# pcb.net
KiCad netlist of a schematic drawn in EAGLE
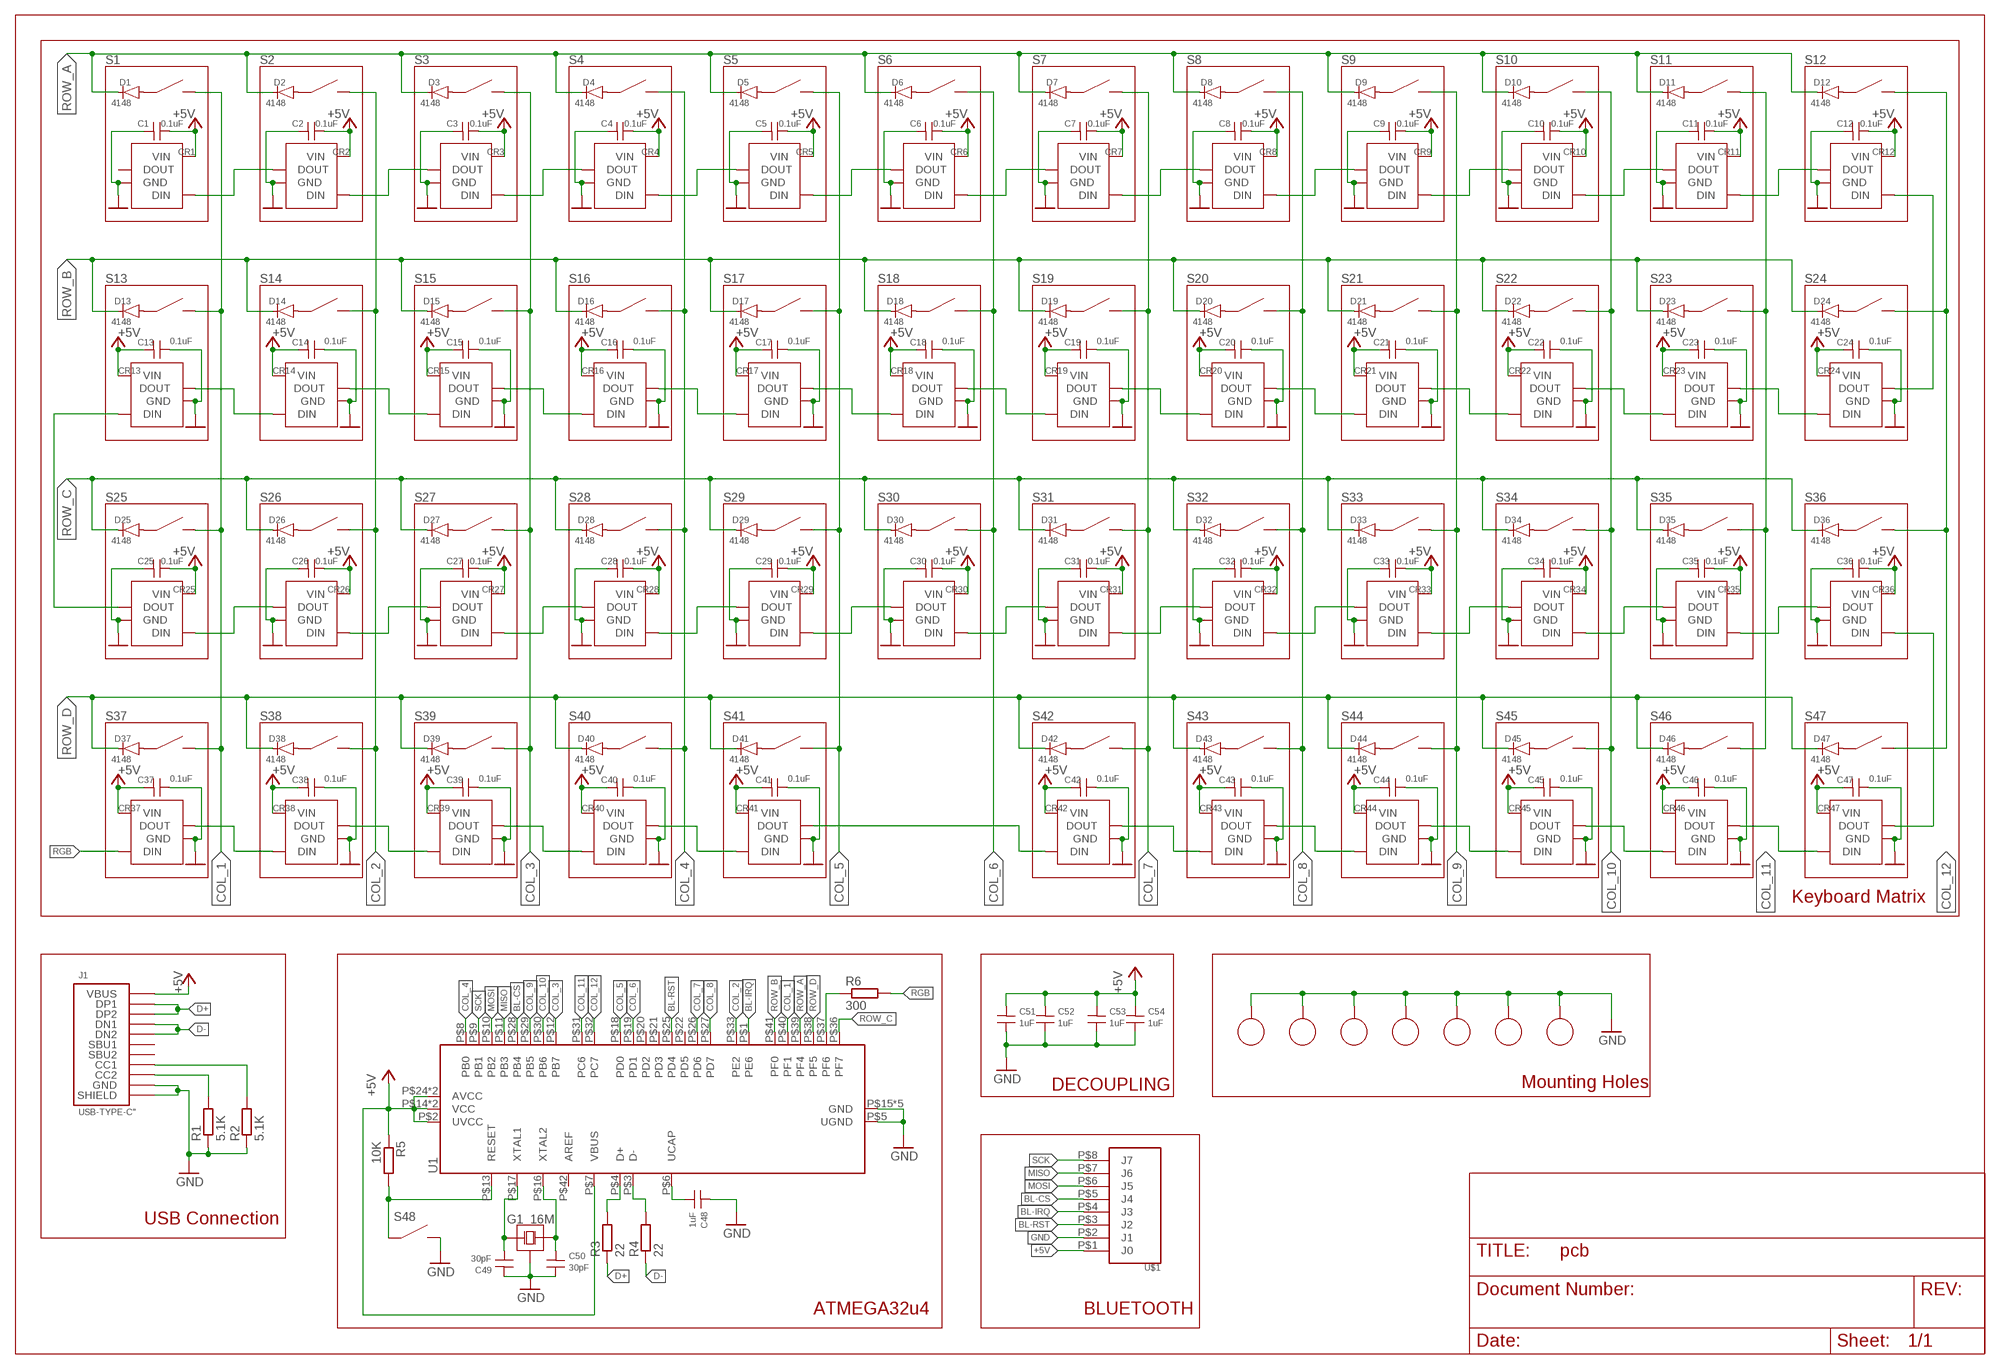
[diagram p0: schematic, sheet 1]

(export (version "E")
  (design (tool "Eeschema 10.0.6"))
  (components
    (comp (ref "C1")
      (value "0.1uF")
      (footprint "eagle-import:C0402")
      (fields
        (field (name "LCSC-PART") "C392963")
        (field (name "MANUFACTURER") "CCTC")
        (field (name "MFGPART#") "TCC0402X7R104K160AT")
      )
      (libsource (lib "eagle-import") (part "C-EU-0402-0.1U"))
    )
    (comp (ref "C2")
      (value "0.1uF")
      (footprint "eagle-import:C0402")
      (fields
        (field (name "LCSC-PART") "C392963")
        (field (name "MANUFACTURER") "CCTC")
        (field (name "MFGPART#") "TCC0402X7R104K160AT")
      )
      (libsource (lib "eagle-import") (part "C-EU-0402-0.1U"))
    )
    (comp (ref "C3")
      (value "0.1uF")
      (footprint "eagle-import:C0402")
      (fields
        (field (name "LCSC-PART") "C392963")
        (field (name "MANUFACTURER") "CCTC")
        (field (name "MFGPART#") "TCC0402X7R104K160AT")
      )
      (libsource (lib "eagle-import") (part "C-EU-0402-0.1U"))
    )
    (comp (ref "C4")
      (value "0.1uF")
      (footprint "eagle-import:C0402")
      (fields
        (field (name "LCSC-PART") "C392963")
        (field (name "MANUFACTURER") "CCTC")
        (field (name "MFGPART#") "TCC0402X7R104K160AT")
      )
      (libsource (lib "eagle-import") (part "C-EU-0402-0.1U"))
    )
    (comp (ref "C5")
      (value "0.1uF")
      (footprint "eagle-import:C0402")
      (fields
        (field (name "LCSC-PART") "C392963")
        (field (name "MANUFACTURER") "CCTC")
        (field (name "MFGPART#") "TCC0402X7R104K160AT")
      )
      (libsource (lib "eagle-import") (part "C-EU-0402-0.1U"))
    )
    (comp (ref "C6")
      (value "0.1uF")
      (footprint "eagle-import:C0402")
      (fields
        (field (name "LCSC-PART") "C392963")
        (field (name "MANUFACTURER") "CCTC")
        (field (name "MFGPART#") "TCC0402X7R104K160AT")
      )
      (libsource (lib "eagle-import") (part "C-EU-0402-0.1U"))
    )
    (comp (ref "C7")
      (value "0.1uF")
      (footprint "eagle-import:C0402")
      (fields
        (field (name "LCSC-PART") "C392963")
        (field (name "MANUFACTURER") "CCTC")
        (field (name "MFGPART#") "TCC0402X7R104K160AT")
      )
      (libsource (lib "eagle-import") (part "C-EU-0402-0.1U"))
    )
    (comp (ref "C8")
      (value "0.1uF")
      (footprint "eagle-import:C0402")
      (fields
        (field (name "LCSC-PART") "C392963")
        (field (name "MANUFACTURER") "CCTC")
        (field (name "MFGPART#") "TCC0402X7R104K160AT")
      )
      (libsource (lib "eagle-import") (part "C-EU-0402-0.1U"))
    )
    (comp (ref "C9")
      (value "0.1uF")
      (footprint "eagle-import:C0402")
      (fields
        (field (name "LCSC-PART") "C392963")
        (field (name "MANUFACTURER") "CCTC")
        (field (name "MFGPART#") "TCC0402X7R104K160AT")
      )
      (libsource (lib "eagle-import") (part "C-EU-0402-0.1U"))
    )
    (comp (ref "C10")
      (value "0.1uF")
      (footprint "eagle-import:C0402")
      (fields
        (field (name "LCSC-PART") "C392963")
        (field (name "MANUFACTURER") "CCTC")
        (field (name "MFGPART#") "TCC0402X7R104K160AT")
      )
      (libsource (lib "eagle-import") (part "C-EU-0402-0.1U"))
    )
    (comp (ref "C11")
      (value "0.1uF")
      (footprint "eagle-import:C0402")
      (fields
        (field (name "LCSC-PART") "C392963")
        (field (name "MANUFACTURER") "CCTC")
        (field (name "MFGPART#") "TCC0402X7R104K160AT")
      )
      (libsource (lib "eagle-import") (part "C-EU-0402-0.1U"))
    )
    (comp (ref "C12")
      (value "0.1uF")
      (footprint "eagle-import:C0402")
      (fields
        (field (name "LCSC-PART") "C392963")
        (field (name "MANUFACTURER") "CCTC")
        (field (name "MFGPART#") "TCC0402X7R104K160AT")
      )
      (libsource (lib "eagle-import") (part "C-EU-0402-0.1U"))
    )
    (comp (ref "C13")
      (value "0.1uF")
      (footprint "eagle-import:C0402")
      (fields
        (field (name "LCSC-PART") "C392963")
        (field (name "MANUFACTURER") "CCTC")
        (field (name "MFGPART#") "TCC0402X7R104K160AT")
      )
      (libsource (lib "eagle-import") (part "C-EU-0402-0.1U"))
    )
    (comp (ref "C14")
      (value "0.1uF")
      (footprint "eagle-import:C0402")
      (fields
        (field (name "LCSC-PART") "C392963")
        (field (name "MANUFACTURER") "CCTC")
        (field (name "MFGPART#") "TCC0402X7R104K160AT")
      )
      (libsource (lib "eagle-import") (part "C-EU-0402-0.1U"))
    )
    (comp (ref "C15")
      (value "0.1uF")
      (footprint "eagle-import:C0402")
      (fields
        (field (name "LCSC-PART") "C392963")
        (field (name "MANUFACTURER") "CCTC")
        (field (name "MFGPART#") "TCC0402X7R104K160AT")
      )
      (libsource (lib "eagle-import") (part "C-EU-0402-0.1U"))
    )
    (comp (ref "C16")
      (value "0.1uF")
      (footprint "eagle-import:C0402")
      (fields
        (field (name "LCSC-PART") "C392963")
        (field (name "MANUFACTURER") "CCTC")
        (field (name "MFGPART#") "TCC0402X7R104K160AT")
      )
      (libsource (lib "eagle-import") (part "C-EU-0402-0.1U"))
    )
    (comp (ref "C17")
      (value "0.1uF")
      (footprint "eagle-import:C0402")
      (fields
        (field (name "LCSC-PART") "C392963")
        (field (name "MANUFACTURER") "CCTC")
        (field (name "MFGPART#") "TCC0402X7R104K160AT")
      )
      (libsource (lib "eagle-import") (part "C-EU-0402-0.1U"))
    )
    (comp (ref "C18")
      (value "0.1uF")
      (footprint "eagle-import:C0402")
      (fields
        (field (name "LCSC-PART") "C392963")
        (field (name "MANUFACTURER") "CCTC")
        (field (name "MFGPART#") "TCC0402X7R104K160AT")
      )
      (libsource (lib "eagle-import") (part "C-EU-0402-0.1U"))
    )
    (comp (ref "C19")
      (value "0.1uF")
      (footprint "eagle-import:C0402")
      (fields
        (field (name "LCSC-PART") "C392963")
        (field (name "MANUFACTURER") "CCTC")
        (field (name "MFGPART#") "TCC0402X7R104K160AT")
      )
      (libsource (lib "eagle-import") (part "C-EU-0402-0.1U"))
    )
    (comp (ref "C20")
      (value "0.1uF")
      (footprint "eagle-import:C0402")
      (fields
        (field (name "LCSC-PART") "C392963")
        (field (name "MANUFACTURER") "CCTC")
        (field (name "MFGPART#") "TCC0402X7R104K160AT")
      )
      (libsource (lib "eagle-import") (part "C-EU-0402-0.1U"))
    )
    (comp (ref "C21")
      (value "0.1uF")
      (footprint "eagle-import:C0402")
      (fields
        (field (name "LCSC-PART") "C392963")
        (field (name "MANUFACTURER") "CCTC")
        (field (name "MFGPART#") "TCC0402X7R104K160AT")
      )
      (libsource (lib "eagle-import") (part "C-EU-0402-0.1U"))
    )
    (comp (ref "C22")
      (value "0.1uF")
      (footprint "eagle-import:C0402")
      (fields
        (field (name "LCSC-PART") "C392963")
        (field (name "MANUFACTURER") "CCTC")
        (field (name "MFGPART#") "TCC0402X7R104K160AT")
      )
      (libsource (lib "eagle-import") (part "C-EU-0402-0.1U"))
    )
    (comp (ref "C23")
      (value "0.1uF")
      (footprint "eagle-import:C0402")
      (fields
        (field (name "LCSC-PART") "C392963")
        (field (name "MANUFACTURER") "CCTC")
        (field (name "MFGPART#") "TCC0402X7R104K160AT")
      )
      (libsource (lib "eagle-import") (part "C-EU-0402-0.1U"))
    )
    (comp (ref "C24")
      (value "0.1uF")
      (footprint "eagle-import:C0402")
      (fields
        (field (name "LCSC-PART") "C392963")
        (field (name "MANUFACTURER") "CCTC")
        (field (name "MFGPART#") "TCC0402X7R104K160AT")
      )
      (libsource (lib "eagle-import") (part "C-EU-0402-0.1U"))
    )
    (comp (ref "C25")
      (value "0.1uF")
      (footprint "eagle-import:C0402")
      (fields
        (field (name "LCSC-PART") "C392963")
        (field (name "MANUFACTURER") "CCTC")
        (field (name "MFGPART#") "TCC0402X7R104K160AT")
      )
      (libsource (lib "eagle-import") (part "C-EU-0402-0.1U"))
    )
    (comp (ref "C26")
      (value "0.1uF")
      (footprint "eagle-import:C0402")
      (fields
        (field (name "LCSC-PART") "C392963")
        (field (name "MANUFACTURER") "CCTC")
        (field (name "MFGPART#") "TCC0402X7R104K160AT")
      )
      (libsource (lib "eagle-import") (part "C-EU-0402-0.1U"))
    )
    (comp (ref "C27")
      (value "0.1uF")
      (footprint "eagle-import:C0402")
      (fields
        (field (name "LCSC-PART") "C392963")
        (field (name "MANUFACTURER") "CCTC")
        (field (name "MFGPART#") "TCC0402X7R104K160AT")
      )
      (libsource (lib "eagle-import") (part "C-EU-0402-0.1U"))
    )
    (comp (ref "C28")
      (value "0.1uF")
      (footprint "eagle-import:C0402")
      (fields
        (field (name "LCSC-PART") "C392963")
        (field (name "MANUFACTURER") "CCTC")
        (field (name "MFGPART#") "TCC0402X7R104K160AT")
      )
      (libsource (lib "eagle-import") (part "C-EU-0402-0.1U"))
    )
    (comp (ref "C29")
      (value "0.1uF")
      (footprint "eagle-import:C0402")
      (fields
        (field (name "LCSC-PART") "C392963")
        (field (name "MANUFACTURER") "CCTC")
        (field (name "MFGPART#") "TCC0402X7R104K160AT")
      )
      (libsource (lib "eagle-import") (part "C-EU-0402-0.1U"))
    )
    (comp (ref "C30")
      (value "0.1uF")
      (footprint "eagle-import:C0402")
      (fields
        (field (name "LCSC-PART") "C392963")
        (field (name "MANUFACTURER") "CCTC")
        (field (name "MFGPART#") "TCC0402X7R104K160AT")
      )
      (libsource (lib "eagle-import") (part "C-EU-0402-0.1U"))
    )
    (comp (ref "C31")
      (value "0.1uF")
      (footprint "eagle-import:C0402")
      (fields
        (field (name "LCSC-PART") "C392963")
        (field (name "MANUFACTURER") "CCTC")
        (field (name "MFGPART#") "TCC0402X7R104K160AT")
      )
      (libsource (lib "eagle-import") (part "C-EU-0402-0.1U"))
    )
    (comp (ref "C32")
      (value "0.1uF")
      (footprint "eagle-import:C0402")
      (fields
        (field (name "LCSC-PART") "C392963")
        (field (name "MANUFACTURER") "CCTC")
        (field (name "MFGPART#") "TCC0402X7R104K160AT")
      )
      (libsource (lib "eagle-import") (part "C-EU-0402-0.1U"))
    )
    (comp (ref "C33")
      (value "0.1uF")
      (footprint "eagle-import:C0402")
      (fields
        (field (name "LCSC-PART") "C392963")
        (field (name "MANUFACTURER") "CCTC")
        (field (name "MFGPART#") "TCC0402X7R104K160AT")
      )
      (libsource (lib "eagle-import") (part "C-EU-0402-0.1U"))
    )
    (comp (ref "C34")
      (value "0.1uF")
      (footprint "eagle-import:C0402")
      (fields
        (field (name "LCSC-PART") "C392963")
        (field (name "MANUFACTURER") "CCTC")
        (field (name "MFGPART#") "TCC0402X7R104K160AT")
      )
      (libsource (lib "eagle-import") (part "C-EU-0402-0.1U"))
    )
    (comp (ref "C35")
      (value "0.1uF")
      (footprint "eagle-import:C0402")
      (fields
        (field (name "LCSC-PART") "C392963")
        (field (name "MANUFACTURER") "CCTC")
        (field (name "MFGPART#") "TCC0402X7R104K160AT")
      )
      (libsource (lib "eagle-import") (part "C-EU-0402-0.1U"))
    )
    (comp (ref "C36")
      (value "0.1uF")
      (footprint "eagle-import:C0402")
      (fields
        (field (name "LCSC-PART") "C392963")
        (field (name "MANUFACTURER") "CCTC")
        (field (name "MFGPART#") "TCC0402X7R104K160AT")
      )
      (libsource (lib "eagle-import") (part "C-EU-0402-0.1U"))
    )
    (comp (ref "C37")
      (value "0.1uF")
      (footprint "eagle-import:C0402")
      (fields
        (field (name "LCSC-PART") "C392963")
        (field (name "MANUFACTURER") "CCTC")
        (field (name "MFGPART#") "TCC0402X7R104K160AT")
      )
      (libsource (lib "eagle-import") (part "C-EU-0402-0.1U"))
    )
    (comp (ref "C38")
      (value "0.1uF")
      (footprint "eagle-import:C0402")
      (fields
        (field (name "LCSC-PART") "C392963")
        (field (name "MANUFACTURER") "CCTC")
        (field (name "MFGPART#") "TCC0402X7R104K160AT")
      )
      (libsource (lib "eagle-import") (part "C-EU-0402-0.1U"))
    )
    (comp (ref "C39")
      (value "0.1uF")
      (footprint "eagle-import:C0402")
      (fields
        (field (name "LCSC-PART") "C392963")
        (field (name "MANUFACTURER") "CCTC")
        (field (name "MFGPART#") "TCC0402X7R104K160AT")
      )
      (libsource (lib "eagle-import") (part "C-EU-0402-0.1U"))
    )
    (comp (ref "C40")
      (value "0.1uF")
      (footprint "eagle-import:C0402")
      (fields
        (field (name "LCSC-PART") "C392963")
        (field (name "MANUFACTURER") "CCTC")
        (field (name "MFGPART#") "TCC0402X7R104K160AT")
      )
      (libsource (lib "eagle-import") (part "C-EU-0402-0.1U"))
    )
    (comp (ref "C41")
      (value "0.1uF")
      (footprint "eagle-import:C0402")
      (fields
        (field (name "LCSC-PART") "C392963")
        (field (name "MANUFACTURER") "CCTC")
        (field (name "MFGPART#") "TCC0402X7R104K160AT")
      )
      (libsource (lib "eagle-import") (part "C-EU-0402-0.1U"))
    )
    (comp (ref "C42")
      (value "0.1uF")
      (footprint "eagle-import:C0402")
      (fields
        (field (name "LCSC-PART") "C392963")
        (field (name "MANUFACTURER") "CCTC")
        (field (name "MFGPART#") "TCC0402X7R104K160AT")
      )
      (libsource (lib "eagle-import") (part "C-EU-0402-0.1U"))
    )
    (comp (ref "C43")
      (value "0.1uF")
      (footprint "eagle-import:C0402")
      (fields
        (field (name "LCSC-PART") "C392963")
        (field (name "MANUFACTURER") "CCTC")
        (field (name "MFGPART#") "TCC0402X7R104K160AT")
      )
      (libsource (lib "eagle-import") (part "C-EU-0402-0.1U"))
    )
    (comp (ref "C44")
      (value "0.1uF")
      (footprint "eagle-import:C0402")
      (fields
        (field (name "LCSC-PART") "C392963")
        (field (name "MANUFACTURER") "CCTC")
        (field (name "MFGPART#") "TCC0402X7R104K160AT")
      )
      (libsource (lib "eagle-import") (part "C-EU-0402-0.1U"))
    )
    (comp (ref "C45")
      (value "0.1uF")
      (footprint "eagle-import:C0402")
      (fields
        (field (name "LCSC-PART") "C392963")
        (field (name "MANUFACTURER") "CCTC")
        (field (name "MFGPART#") "TCC0402X7R104K160AT")
      )
      (libsource (lib "eagle-import") (part "C-EU-0402-0.1U"))
    )
    (comp (ref "C46")
      (value "0.1uF")
      (footprint "eagle-import:C0402")
      (fields
        (field (name "LCSC-PART") "C392963")
        (field (name "MANUFACTURER") "CCTC")
        (field (name "MFGPART#") "TCC0402X7R104K160AT")
      )
      (libsource (lib "eagle-import") (part "C-EU-0402-0.1U"))
    )
    (comp (ref "C47")
      (value "0.1uF")
      (footprint "eagle-import:C0402")
      (fields
        (field (name "LCSC-PART") "C392963")
        (field (name "MANUFACTURER") "CCTC")
        (field (name "MFGPART#") "TCC0402X7R104K160AT")
      )
      (libsource (lib "eagle-import") (part "C-EU-0402-0.1U"))
    )
    (comp (ref "C48")
      (value "1uF")
      (footprint "eagle-import:C0402")
      (fields
        (field (name "LCSC-PART") "C107372")
        (field (name "MANUFACTURER") "Samsung Electro-Mechanics")
        (field (name "MFGPART#") "CL05A105KQ5NNNC")
      )
      (libsource (lib "eagle-import") (part "C-EU-0402-1U"))
    )
    (comp (ref "C49")
      (value "30pF")
      (footprint "eagle-import:C0402")
      (fields
        (field (name "LCSC-PART") "C107004")
        (field (name "MANUFACTURER") "YAGEO")
        (field (name "MFGPART#") "CC0402JRNPO9BN300")
      )
      (libsource (lib "eagle-import") (part "C-EU-0402-30P"))
    )
    (comp (ref "C50")
      (value "30pF")
      (footprint "eagle-import:C0402")
      (fields
        (field (name "LCSC-PART") "C107004")
        (field (name "MANUFACTURER") "YAGEO")
        (field (name "MFGPART#") "CC0402JRNPO9BN300")
      )
      (libsource (lib "eagle-import") (part "C-EU-0402-30P"))
    )
    (comp (ref "C51")
      (value "1uF")
      (footprint "eagle-import:C0402")
      (fields
        (field (name "LCSC-PART") "C107372")
        (field (name "MANUFACTURER") "Samsung Electro-Mechanics")
        (field (name "MFGPART#") "CL05A105KQ5NNNC")
      )
      (libsource (lib "eagle-import") (part "C-EU-0402-1U"))
    )
    (comp (ref "C52")
      (value "1uF")
      (footprint "eagle-import:C0402")
      (fields
        (field (name "LCSC-PART") "C107372")
        (field (name "MANUFACTURER") "Samsung Electro-Mechanics")
        (field (name "MFGPART#") "CL05A105KQ5NNNC")
      )
      (libsource (lib "eagle-import") (part "C-EU-0402-1U"))
    )
    (comp (ref "C53")
      (value "1uF")
      (footprint "eagle-import:C0402")
      (fields
        (field (name "LCSC-PART") "C107372")
        (field (name "MANUFACTURER") "Samsung Electro-Mechanics")
        (field (name "MFGPART#") "CL05A105KQ5NNNC")
      )
      (libsource (lib "eagle-import") (part "C-EU-0402-1U"))
    )
    (comp (ref "C54")
      (value "1uF")
      (footprint "eagle-import:C0402")
      (fields
        (field (name "LCSC-PART") "C107372")
        (field (name "MANUFACTURER") "Samsung Electro-Mechanics")
        (field (name "MFGPART#") "CL05A105KQ5NNNC")
      )
      (libsource (lib "eagle-import") (part "C-EU-0402-1U"))
    )
    (comp (ref "CR1")
      (value "SK6812MINI-E")
      (footprint "eagle-import:SK6812MINI-E")
      (fields (field (name "SPICEPREFIX") "E"))
      (libsource (lib "eagle-import") (part "SK6812MINI-E"))
    )
    (comp (ref "CR2")
      (value "SK6812MINI-E")
      (footprint "eagle-import:SK6812MINI-E")
      (fields (field (name "SPICEPREFIX") "E"))
      (libsource (lib "eagle-import") (part "SK6812MINI-E"))
    )
    (comp (ref "CR3")
      (value "SK6812MINI-E")
      (footprint "eagle-import:SK6812MINI-E")
      (fields (field (name "SPICEPREFIX") "E"))
      (libsource (lib "eagle-import") (part "SK6812MINI-E"))
    )
    (comp (ref "CR4")
      (value "SK6812MINI-E")
      (footprint "eagle-import:SK6812MINI-E")
      (fields (field (name "SPICEPREFIX") "E"))
      (libsource (lib "eagle-import") (part "SK6812MINI-E"))
    )
    (comp (ref "CR5")
      (value "SK6812MINI-E")
      (footprint "eagle-import:SK6812MINI-E")
      (fields (field (name "SPICEPREFIX") "E"))
      (libsource (lib "eagle-import") (part "SK6812MINI-E"))
    )
    (comp (ref "CR6")
      (value "SK6812MINI-E")
      (footprint "eagle-import:SK6812MINI-E")
      (fields (field (name "SPICEPREFIX") "E"))
      (libsource (lib "eagle-import") (part "SK6812MINI-E"))
    )
    (comp (ref "CR7")
      (value "SK6812MINI-E")
      (footprint "eagle-import:SK6812MINI-E")
      (fields (field (name "SPICEPREFIX") "E"))
      (libsource (lib "eagle-import") (part "SK6812MINI-E"))
    )
    (comp (ref "CR8")
      (value "SK6812MINI-E")
      (footprint "eagle-import:SK6812MINI-E")
      (fields (field (name "SPICEPREFIX") "E"))
      (libsource (lib "eagle-import") (part "SK6812MINI-E"))
    )
    (comp (ref "CR9")
      (value "SK6812MINI-E")
      (footprint "eagle-import:SK6812MINI-E")
      (fields (field (name "SPICEPREFIX") "E"))
      (libsource (lib "eagle-import") (part "SK6812MINI-E"))
    )
    (comp (ref "CR10")
      (value "SK6812MINI-E")
      (footprint "eagle-import:SK6812MINI-E")
      (fields (field (name "SPICEPREFIX") "E"))
      (libsource (lib "eagle-import") (part "SK6812MINI-E"))
    )
    (comp (ref "CR11")
      (value "SK6812MINI-E")
      (footprint "eagle-import:SK6812MINI-E")
      (fields (field (name "SPICEPREFIX") "E"))
      (libsource (lib "eagle-import") (part "SK6812MINI-E"))
    )
    (comp (ref "CR12")
      (value "SK6812MINI-E")
      (footprint "eagle-import:SK6812MINI-E")
      (fields (field (name "SPICEPREFIX") "E"))
      (libsource (lib "eagle-import") (part "SK6812MINI-E"))
    )
    (comp (ref "CR13")
      (value "SK6812MINI-E")
      (footprint "eagle-import:SK6812MINI-E")
      (fields (field (name "SPICEPREFIX") "E"))
      (libsource (lib "eagle-import") (part "SK6812MINI-E"))
    )
    (comp (ref "CR14")
      (value "SK6812MINI-E")
      (footprint "eagle-import:SK6812MINI-E")
      (fields (field (name "SPICEPREFIX") "E"))
      (libsource (lib "eagle-import") (part "SK6812MINI-E"))
    )
    (comp (ref "CR15")
      (value "SK6812MINI-E")
      (footprint "eagle-import:SK6812MINI-E")
      (fields (field (name "SPICEPREFIX") "E"))
      (libsource (lib "eagle-import") (part "SK6812MINI-E"))
    )
    (comp (ref "CR16")
      (value "SK6812MINI-E")
      (footprint "eagle-import:SK6812MINI-E")
      (fields (field (name "SPICEPREFIX") "E"))
      (libsource (lib "eagle-import") (part "SK6812MINI-E"))
    )
    (comp (ref "CR17")
      (value "SK6812MINI-E")
      (footprint "eagle-import:SK6812MINI-E")
      (fields (field (name "SPICEPREFIX") "E"))
      (libsource (lib "eagle-import") (part "SK6812MINI-E"))
    )
    (comp (ref "CR18")
      (value "SK6812MINI-E")
      (footprint "eagle-import:SK6812MINI-E")
      (fields (field (name "SPICEPREFIX") "E"))
      (libsource (lib "eagle-import") (part "SK6812MINI-E"))
    )
    (comp (ref "CR19")
      (value "SK6812MINI-E")
      (footprint "eagle-import:SK6812MINI-E")
      (fields (field (name "SPICEPREFIX") "E"))
      (libsource (lib "eagle-import") (part "SK6812MINI-E"))
    )
    (comp (ref "CR20")
      (value "SK6812MINI-E")
      (footprint "eagle-import:SK6812MINI-E")
      (fields (field (name "SPICEPREFIX") "E"))
      (libsource (lib "eagle-import") (part "SK6812MINI-E"))
    )
    (comp (ref "CR21")
      (value "SK6812MINI-E")
      (footprint "eagle-import:SK6812MINI-E")
      (fields (field (name "SPICEPREFIX") "E"))
      (libsource (lib "eagle-import") (part "SK6812MINI-E"))
    )
    (comp (ref "CR22")
      (value "SK6812MINI-E")
      (footprint "eagle-import:SK6812MINI-E")
      (fields (field (name "SPICEPREFIX") "E"))
      (libsource (lib "eagle-import") (part "SK6812MINI-E"))
    )
    (comp (ref "CR23")
      (value "SK6812MINI-E")
      (footprint "eagle-import:SK6812MINI-E")
      (fields (field (name "SPICEPREFIX") "E"))
      (libsource (lib "eagle-import") (part "SK6812MINI-E"))
    )
    (comp (ref "CR24")
      (value "SK6812MINI-E")
      (footprint "eagle-import:SK6812MINI-E")
      (fields (field (name "SPICEPREFIX") "E"))
      (libsource (lib "eagle-import") (part "SK6812MINI-E"))
    )
    (comp (ref "CR25")
      (value "SK6812MINI-E")
      (footprint "eagle-import:SK6812MINI-E")
      (fields (field (name "SPICEPREFIX") "E"))
      (libsource (lib "eagle-import") (part "SK6812MINI-E"))
    )
    (comp (ref "CR26")
      (value "SK6812MINI-E")
      (footprint "eagle-import:SK6812MINI-E")
      (fields (field (name "SPICEPREFIX") "E"))
      (libsource (lib "eagle-import") (part "SK6812MINI-E"))
    )
    (comp (ref "CR27")
      (value "SK6812MINI-E")
      (footprint "eagle-import:SK6812MINI-E")
      (fields (field (name "SPICEPREFIX") "E"))
      (libsource (lib "eagle-import") (part "SK6812MINI-E"))
    )
    (comp (ref "CR28")
      (value "SK6812MINI-E")
      (footprint "eagle-import:SK6812MINI-E")
      (fields (field (name "SPICEPREFIX") "E"))
      (libsource (lib "eagle-import") (part "SK6812MINI-E"))
    )
    (comp (ref "CR29")
      (value "SK6812MINI-E")
      (footprint "eagle-import:SK6812MINI-E")
      (fields (field (name "SPICEPREFIX") "E"))
      (libsource (lib "eagle-import") (part "SK6812MINI-E"))
    )
    (comp (ref "CR30")
      (value "SK6812MINI-E")
      (footprint "eagle-import:SK6812MINI-E")
      (fields (field (name "SPICEPREFIX") "E"))
      (libsource (lib "eagle-import") (part "SK6812MINI-E"))
    )
    (comp (ref "CR31")
      (value "SK6812MINI-E")
      (footprint "eagle-import:SK6812MINI-E")
      (fields (field (name "SPICEPREFIX") "E"))
      (libsource (lib "eagle-import") (part "SK6812MINI-E"))
    )
    (comp (ref "CR32")
      (value "SK6812MINI-E")
      (footprint "eagle-import:SK6812MINI-E")
      (fields (field (name "SPICEPREFIX") "E"))
      (libsource (lib "eagle-import") (part "SK6812MINI-E"))
    )
    (comp (ref "CR33")
      (value "SK6812MINI-E")
      (footprint "eagle-import:SK6812MINI-E")
      (fields (field (name "SPICEPREFIX") "E"))
      (libsource (lib "eagle-import") (part "SK6812MINI-E"))
    )
    (comp (ref "CR34")
      (value "SK6812MINI-E")
      (footprint "eagle-import:SK6812MINI-E")
      (fields (field (name "SPICEPREFIX") "E"))
      (libsource (lib "eagle-import") (part "SK6812MINI-E"))
    )
    (comp (ref "CR35")
      (value "SK6812MINI-E")
      (footprint "eagle-import:SK6812MINI-E")
      (fields (field (name "SPICEPREFIX") "E"))
      (libsource (lib "eagle-import") (part "SK6812MINI-E"))
    )
    (comp (ref "CR36")
      (value "SK6812MINI-E")
      (footprint "eagle-import:SK6812MINI-E")
      (fields (field (name "SPICEPREFIX") "E"))
      (libsource (lib "eagle-import") (part "SK6812MINI-E"))
    )
    (comp (ref "CR37")
      (value "SK6812MINI-E")
      (footprint "eagle-import:SK6812MINI-E")
      (fields (field (name "SPICEPREFIX") "E"))
      (libsource (lib "eagle-import") (part "SK6812MINI-E"))
    )
    (comp (ref "CR38")
      (value "SK6812MINI-E")
      (footprint "eagle-import:SK6812MINI-E")
      (fields (field (name "SPICEPREFIX") "E"))
      (libsource (lib "eagle-import") (part "SK6812MINI-E"))
    )
    (comp (ref "CR39")
      (value "SK6812MINI-E")
      (footprint "eagle-import:SK6812MINI-E")
      (fields (field (name "SPICEPREFIX") "E"))
      (libsource (lib "eagle-import") (part "SK6812MINI-E"))
    )
    (comp (ref "CR40")
      (value "SK6812MINI-E")
      (footprint "eagle-import:SK6812MINI-E")
      (fields (field (name "SPICEPREFIX") "E"))
      (libsource (lib "eagle-import") (part "SK6812MINI-E"))
    )
    (comp (ref "CR41")
      (value "SK6812MINI-E")
      (footprint "eagle-import:SK6812MINI-E")
      (fields (field (name "SPICEPREFIX") "E"))
      (libsource (lib "eagle-import") (part "SK6812MINI-E"))
    )
    (comp (ref "CR42")
      (value "SK6812MINI-E")
      (footprint "eagle-import:SK6812MINI-E")
      (fields (field (name "SPICEPREFIX") "E"))
      (libsource (lib "eagle-import") (part "SK6812MINI-E"))
    )
    (comp (ref "CR43")
      (value "SK6812MINI-E")
      (footprint "eagle-import:SK6812MINI-E")
      (fields (field (name "SPICEPREFIX") "E"))
      (libsource (lib "eagle-import") (part "SK6812MINI-E"))
    )
    (comp (ref "CR44")
      (value "SK6812MINI-E")
      (footprint "eagle-import:SK6812MINI-E")
      (fields (field (name "SPICEPREFIX") "E"))
      (libsource (lib "eagle-import") (part "SK6812MINI-E"))
    )
    (comp (ref "CR45")
      (value "SK6812MINI-E")
      (footprint "eagle-import:SK6812MINI-E")
      (fields (field (name "SPICEPREFIX") "E"))
      (libsource (lib "eagle-import") (part "SK6812MINI-E"))
    )
    (comp (ref "CR46")
      (value "SK6812MINI-E")
      (footprint "eagle-import:SK6812MINI-E")
      (fields (field (name "SPICEPREFIX") "E"))
      (libsource (lib "eagle-import") (part "SK6812MINI-E"))
    )
    (comp (ref "CR47")
      (value "SK6812MINI-E")
      (footprint "eagle-import:SK6812MINI-E")
      (fields (field (name "SPICEPREFIX") "E"))
      (libsource (lib "eagle-import") (part "SK6812MINI-E"))
    )
    (comp (ref "D1")
      (value "4148")
      (footprint "eagle-import:MINI_MELF")
      (fields
        (field (name "LCSC-PART") "C402260")
        (field (name "MANUFACTURER") "LGE")
        (field (name "MFGPART#") "LL4148")
        (field (name "SPICEPREFIX") "D")
      )
      (libsource (lib "eagle-import") (part "DIODE-MINI-MELF-4148"))
    )
    (comp (ref "D2")
      (value "4148")
      (footprint "eagle-import:MINI_MELF")
      (fields
        (field (name "LCSC-PART") "C402260")
        (field (name "MANUFACTURER") "LGE")
        (field (name "MFGPART#") "LL4148")
        (field (name "SPICEPREFIX") "D")
      )
      (libsource (lib "eagle-import") (part "DIODE-MINI-MELF-4148"))
    )
    (comp (ref "D3")
      (value "4148")
      (footprint "eagle-import:MINI_MELF")
      (fields
        (field (name "LCSC-PART") "C402260")
        (field (name "MANUFACTURER") "LGE")
        (field (name "MFGPART#") "LL4148")
        (field (name "SPICEPREFIX") "D")
      )
      (libsource (lib "eagle-import") (part "DIODE-MINI-MELF-4148"))
    )
    (comp (ref "D4")
      (value "4148")
      (footprint "eagle-import:MINI_MELF")
      (fields
        (field (name "LCSC-PART") "C402260")
        (field (name "MANUFACTURER") "LGE")
        (field (name "MFGPART#") "LL4148")
        (field (name "SPICEPREFIX") "D")
      )
      (libsource (lib "eagle-import") (part "DIODE-MINI-MELF-4148"))
    )
    (comp (ref "D5")
      (value "4148")
      (footprint "eagle-import:MINI_MELF")
      (fields
        (field (name "LCSC-PART") "C402260")
        (field (name "MANUFACTURER") "LGE")
        (field (name "MFGPART#") "LL4148")
        (field (name "SPICEPREFIX") "D")
      )
      (libsource (lib "eagle-import") (part "DIODE-MINI-MELF-4148"))
    )
    (comp (ref "D6")
      (value "4148")
      (footprint "eagle-import:MINI_MELF")
      (fields
        (field (name "LCSC-PART") "C402260")
        (field (name "MANUFACTURER") "LGE")
        (field (name "MFGPART#") "LL4148")
        (field (name "SPICEPREFIX") "D")
      )
      (libsource (lib "eagle-import") (part "DIODE-MINI-MELF-4148"))
    )
    (comp (ref "D7")
      (value "4148")
      (footprint "eagle-import:MINI_MELF")
      (fields
        (field (name "LCSC-PART") "C402260")
        (field (name "MANUFACTURER") "LGE")
        (field (name "MFGPART#") "LL4148")
        (field (name "SPICEPREFIX") "D")
      )
      (libsource (lib "eagle-import") (part "DIODE-MINI-MELF-4148"))
    )
    (comp (ref "D8")
      (value "4148")
      (footprint "eagle-import:MINI_MELF")
      (fields
        (field (name "LCSC-PART") "C402260")
        (field (name "MANUFACTURER") "LGE")
        (field (name "MFGPART#") "LL4148")
        (field (name "SPICEPREFIX") "D")
      )
      (libsource (lib "eagle-import") (part "DIODE-MINI-MELF-4148"))
    )
    (comp (ref "D9")
      (value "4148")
      (footprint "eagle-import:MINI_MELF")
      (fields
        (field (name "LCSC-PART") "C402260")
        (field (name "MANUFACTURER") "LGE")
        (field (name "MFGPART#") "LL4148")
        (field (name "SPICEPREFIX") "D")
      )
      (libsource (lib "eagle-import") (part "DIODE-MINI-MELF-4148"))
    )
    (comp (ref "D10")
      (value "4148")
      (footprint "eagle-import:MINI_MELF")
      (fields
        (field (name "LCSC-PART") "C402260")
        (field (name "MANUFACTURER") "LGE")
        (field (name "MFGPART#") "LL4148")
        (field (name "SPICEPREFIX") "D")
      )
      (libsource (lib "eagle-import") (part "DIODE-MINI-MELF-4148"))
    )
    (comp (ref "D11")
      (value "4148")
      (footprint "eagle-import:MINI_MELF")
      (fields
        (field (name "LCSC-PART") "C402260")
        (field (name "MANUFACTURER") "LGE")
        (field (name "MFGPART#") "LL4148")
        (field (name "SPICEPREFIX") "D")
      )
      (libsource (lib "eagle-import") (part "DIODE-MINI-MELF-4148"))
    )
    (comp (ref "D12")
      (value "4148")
      (footprint "eagle-import:MINI_MELF")
      (fields
        (field (name "LCSC-PART") "C402260")
        (field (name "MANUFACTURER") "LGE")
        (field (name "MFGPART#") "LL4148")
        (field (name "SPICEPREFIX") "D")
      )
      (libsource (lib "eagle-import") (part "DIODE-MINI-MELF-4148"))
    )
    (comp (ref "D13")
      (value "4148")
      (footprint "eagle-import:MINI_MELF")
      (fields
        (field (name "LCSC-PART") "C402260")
        (field (name "MANUFACTURER") "LGE")
        (field (name "MFGPART#") "LL4148")
        (field (name "SPICEPREFIX") "D")
      )
      (libsource (lib "eagle-import") (part "DIODE-MINI-MELF-4148"))
    )
    (comp (ref "D14")
      (value "4148")
      (footprint "eagle-import:MINI_MELF")
      (fields
        (field (name "LCSC-PART") "C402260")
        (field (name "MANUFACTURER") "LGE")
        (field (name "MFGPART#") "LL4148")
        (field (name "SPICEPREFIX") "D")
      )
      (libsource (lib "eagle-import") (part "DIODE-MINI-MELF-4148"))
    )
    (comp (ref "D15")
      (value "4148")
      (footprint "eagle-import:MINI_MELF")
      (fields
        (field (name "LCSC-PART") "C402260")
        (field (name "MANUFACTURER") "LGE")
        (field (name "MFGPART#") "LL4148")
        (field (name "SPICEPREFIX") "D")
      )
      (libsource (lib "eagle-import") (part "DIODE-MINI-MELF-4148"))
    )
    (comp (ref "D16")
      (value "4148")
      (footprint "eagle-import:MINI_MELF")
      (fields
        (field (name "LCSC-PART") "C402260")
        (field (name "MANUFACTURER") "LGE")
        (field (name "MFGPART#") "LL4148")
        (field (name "SPICEPREFIX") "D")
      )
      (libsource (lib "eagle-import") (part "DIODE-MINI-MELF-4148"))
    )
    (comp (ref "D17")
      (value "4148")
      (footprint "eagle-import:MINI_MELF")
      (fields
        (field (name "LCSC-PART") "C402260")
        (field (name "MANUFACTURER") "LGE")
        (field (name "MFGPART#") "LL4148")
        (field (name "SPICEPREFIX") "D")
      )
      (libsource (lib "eagle-import") (part "DIODE-MINI-MELF-4148"))
    )
    (comp (ref "D18")
      (value "4148")
      (footprint "eagle-import:MINI_MELF")
      (fields
        (field (name "LCSC-PART") "C402260")
        (field (name "MANUFACTURER") "LGE")
        (field (name "MFGPART#") "LL4148")
        (field (name "SPICEPREFIX") "D")
      )
      (libsource (lib "eagle-import") (part "DIODE-MINI-MELF-4148"))
    )
    (comp (ref "D19")
      (value "4148")
      (footprint "eagle-import:MINI_MELF")
      (fields
        (field (name "LCSC-PART") "C402260")
        (field (name "MANUFACTURER") "LGE")
        (field (name "MFGPART#") "LL4148")
        (field (name "SPICEPREFIX") "D")
      )
      (libsource (lib "eagle-import") (part "DIODE-MINI-MELF-4148"))
    )
    (comp (ref "D20")
      (value "4148")
      (footprint "eagle-import:MINI_MELF")
      (fields
        (field (name "LCSC-PART") "C402260")
        (field (name "MANUFACTURER") "LGE")
        (field (name "MFGPART#") "LL4148")
        (field (name "SPICEPREFIX") "D")
      )
      (libsource (lib "eagle-import") (part "DIODE-MINI-MELF-4148"))
    )
    (comp (ref "D21")
      (value "4148")
      (footprint "eagle-import:MINI_MELF")
      (fields
        (field (name "LCSC-PART") "C402260")
        (field (name "MANUFACTURER") "LGE")
        (field (name "MFGPART#") "LL4148")
        (field (name "SPICEPREFIX") "D")
      )
      (libsource (lib "eagle-import") (part "DIODE-MINI-MELF-4148"))
    )
    (comp (ref "D22")
      (value "4148")
      (footprint "eagle-import:MINI_MELF")
      (fields
        (field (name "LCSC-PART") "C402260")
        (field (name "MANUFACTURER") "LGE")
        (field (name "MFGPART#") "LL4148")
        (field (name "SPICEPREFIX") "D")
      )
      (libsource (lib "eagle-import") (part "DIODE-MINI-MELF-4148"))
    )
    (comp (ref "D23")
      (value "4148")
      (footprint "eagle-import:MINI_MELF")
      (fields
        (field (name "LCSC-PART") "C402260")
        (field (name "MANUFACTURER") "LGE")
        (field (name "MFGPART#") "LL4148")
        (field (name "SPICEPREFIX") "D")
      )
      (libsource (lib "eagle-import") (part "DIODE-MINI-MELF-4148"))
    )
    (comp (ref "D24")
      (value "4148")
      (footprint "eagle-import:MINI_MELF")
      (fields
        (field (name "LCSC-PART") "C402260")
        (field (name "MANUFACTURER") "LGE")
        (field (name "MFGPART#") "LL4148")
        (field (name "SPICEPREFIX") "D")
      )
      (libsource (lib "eagle-import") (part "DIODE-MINI-MELF-4148"))
    )
    (comp (ref "D25")
      (value "4148")
      (footprint "eagle-import:MINI_MELF")
      (fields
        (field (name "LCSC-PART") "C402260")
        (field (name "MANUFACTURER") "LGE")
        (field (name "MFGPART#") "LL4148")
        (field (name "SPICEPREFIX") "D")
      )
      (libsource (lib "eagle-import") (part "DIODE-MINI-MELF-4148"))
    )
    (comp (ref "D26")
      (value "4148")
      (footprint "eagle-import:MINI_MELF")
      (fields
        (field (name "LCSC-PART") "C402260")
        (field (name "MANUFACTURER") "LGE")
        (field (name "MFGPART#") "LL4148")
        (field (name "SPICEPREFIX") "D")
      )
      (libsource (lib "eagle-import") (part "DIODE-MINI-MELF-4148"))
    )
    (comp (ref "D27")
      (value "4148")
      (footprint "eagle-import:MINI_MELF")
      (fields
        (field (name "LCSC-PART") "C402260")
        (field (name "MANUFACTURER") "LGE")
        (field (name "MFGPART#") "LL4148")
        (field (name "SPICEPREFIX") "D")
      )
      (libsource (lib "eagle-import") (part "DIODE-MINI-MELF-4148"))
    )
    (comp (ref "D28")
      (value "4148")
      (footprint "eagle-import:MINI_MELF")
      (fields
        (field (name "LCSC-PART") "C402260")
        (field (name "MANUFACTURER") "LGE")
        (field (name "MFGPART#") "LL4148")
        (field (name "SPICEPREFIX") "D")
      )
      (libsource (lib "eagle-import") (part "DIODE-MINI-MELF-4148"))
    )
    (comp (ref "D29")
      (value "4148")
      (footprint "eagle-import:MINI_MELF")
      (fields
        (field (name "LCSC-PART") "C402260")
        (field (name "MANUFACTURER") "LGE")
        (field (name "MFGPART#") "LL4148")
        (field (name "SPICEPREFIX") "D")
      )
      (libsource (lib "eagle-import") (part "DIODE-MINI-MELF-4148"))
    )
    (comp (ref "D30")
      (value "4148")
      (footprint "eagle-import:MINI_MELF")
      (fields
        (field (name "LCSC-PART") "C402260")
        (field (name "MANUFACTURER") "LGE")
        (field (name "MFGPART#") "LL4148")
        (field (name "SPICEPREFIX") "D")
      )
      (libsource (lib "eagle-import") (part "DIODE-MINI-MELF-4148"))
    )
    (comp (ref "D31")
      (value "4148")
      (footprint "eagle-import:MINI_MELF")
      (fields
        (field (name "LCSC-PART") "C402260")
        (field (name "MANUFACTURER") "LGE")
        (field (name "MFGPART#") "LL4148")
        (field (name "SPICEPREFIX") "D")
      )
      (libsource (lib "eagle-import") (part "DIODE-MINI-MELF-4148"))
    )
    (comp (ref "D32")
      (value "4148")
      (footprint "eagle-import:MINI_MELF")
      (fields
        (field (name "LCSC-PART") "C402260")
        (field (name "MANUFACTURER") "LGE")
        (field (name "MFGPART#") "LL4148")
        (field (name "SPICEPREFIX") "D")
      )
      (libsource (lib "eagle-import") (part "DIODE-MINI-MELF-4148"))
    )
    (comp (ref "D33")
      (value "4148")
      (footprint "eagle-import:MINI_MELF")
      (fields
        (field (name "LCSC-PART") "C402260")
        (field (name "MANUFACTURER") "LGE")
        (field (name "MFGPART#") "LL4148")
        (field (name "SPICEPREFIX") "D")
      )
      (libsource (lib "eagle-import") (part "DIODE-MINI-MELF-4148"))
    )
    (comp (ref "D34")
      (value "4148")
      (footprint "eagle-import:MINI_MELF")
      (fields
        (field (name "LCSC-PART") "C402260")
        (field (name "MANUFACTURER") "LGE")
        (field (name "MFGPART#") "LL4148")
        (field (name "SPICEPREFIX") "D")
      )
      (libsource (lib "eagle-import") (part "DIODE-MINI-MELF-4148"))
    )
    (comp (ref "D35")
      (value "4148")
      (footprint "eagle-import:MINI_MELF")
      (fields
        (field (name "LCSC-PART") "C402260")
        (field (name "MANUFACTURER") "LGE")
        (field (name "MFGPART#") "LL4148")
        (field (name "SPICEPREFIX") "D")
      )
      (libsource (lib "eagle-import") (part "DIODE-MINI-MELF-4148"))
    )
    (comp (ref "D36")
      (value "4148")
      (footprint "eagle-import:MINI_MELF")
      (fields
        (field (name "LCSC-PART") "C402260")
        (field (name "MANUFACTURER") "LGE")
        (field (name "MFGPART#") "LL4148")
        (field (name "SPICEPREFIX") "D")
      )
      (libsource (lib "eagle-import") (part "DIODE-MINI-MELF-4148"))
    )
    (comp (ref "D37")
      (value "4148")
      (footprint "eagle-import:MINI_MELF")
      (fields
        (field (name "LCSC-PART") "C402260")
        (field (name "MANUFACTURER") "LGE")
        (field (name "MFGPART#") "LL4148")
        (field (name "SPICEPREFIX") "D")
      )
      (libsource (lib "eagle-import") (part "DIODE-MINI-MELF-4148"))
    )
    (comp (ref "D38")
      (value "4148")
      (footprint "eagle-import:MINI_MELF")
      (fields
        (field (name "LCSC-PART") "C402260")
        (field (name "MANUFACTURER") "LGE")
        (field (name "MFGPART#") "LL4148")
        (field (name "SPICEPREFIX") "D")
      )
      (libsource (lib "eagle-import") (part "DIODE-MINI-MELF-4148"))
    )
    (comp (ref "D39")
      (value "4148")
      (footprint "eagle-import:MINI_MELF")
      (fields
        (field (name "LCSC-PART") "C402260")
        (field (name "MANUFACTURER") "LGE")
        (field (name "MFGPART#") "LL4148")
        (field (name "SPICEPREFIX") "D")
      )
      (libsource (lib "eagle-import") (part "DIODE-MINI-MELF-4148"))
    )
    (comp (ref "D40")
      (value "4148")
      (footprint "eagle-import:MINI_MELF")
      (fields
        (field (name "LCSC-PART") "C402260")
        (field (name "MANUFACTURER") "LGE")
        (field (name "MFGPART#") "LL4148")
        (field (name "SPICEPREFIX") "D")
      )
      (libsource (lib "eagle-import") (part "DIODE-MINI-MELF-4148"))
    )
    (comp (ref "D41")
      (value "4148")
      (footprint "eagle-import:MINI_MELF")
      (fields
        (field (name "LCSC-PART") "C402260")
        (field (name "MANUFACTURER") "LGE")
        (field (name "MFGPART#") "LL4148")
        (field (name "SPICEPREFIX") "D")
      )
      (libsource (lib "eagle-import") (part "DIODE-MINI-MELF-4148"))
    )
    (comp (ref "D42")
      (value "4148")
      (footprint "eagle-import:MINI_MELF")
      (fields
        (field (name "LCSC-PART") "C402260")
        (field (name "MANUFACTURER") "LGE")
        (field (name "MFGPART#") "LL4148")
        (field (name "SPICEPREFIX") "D")
      )
      (libsource (lib "eagle-import") (part "DIODE-MINI-MELF-4148"))
    )
    (comp (ref "D43")
      (value "4148")
      (footprint "eagle-import:MINI_MELF")
      (fields
        (field (name "LCSC-PART") "C402260")
        (field (name "MANUFACTURER") "LGE")
        (field (name "MFGPART#") "LL4148")
        (field (name "SPICEPREFIX") "D")
      )
      (libsource (lib "eagle-import") (part "DIODE-MINI-MELF-4148"))
    )
    (comp (ref "D44")
      (value "4148")
      (footprint "eagle-import:MINI_MELF")
      (fields
        (field (name "LCSC-PART") "C402260")
        (field (name "MANUFACTURER") "LGE")
        (field (name "MFGPART#") "LL4148")
        (field (name "SPICEPREFIX") "D")
      )
      (libsource (lib "eagle-import") (part "DIODE-MINI-MELF-4148"))
    )
    (comp (ref "D45")
      (value "4148")
      (footprint "eagle-import:MINI_MELF")
      (fields
        (field (name "LCSC-PART") "C402260")
        (field (name "MANUFACTURER") "LGE")
        (field (name "MFGPART#") "LL4148")
        (field (name "SPICEPREFIX") "D")
      )
      (libsource (lib "eagle-import") (part "DIODE-MINI-MELF-4148"))
    )
    (comp (ref "D46")
      (value "4148")
      (footprint "eagle-import:MINI_MELF")
      (fields
        (field (name "LCSC-PART") "C402260")
        (field (name "MANUFACTURER") "LGE")
        (field (name "MFGPART#") "LL4148")
        (field (name "SPICEPREFIX") "D")
      )
      (libsource (lib "eagle-import") (part "DIODE-MINI-MELF-4148"))
    )
    (comp (ref "D47")
      (value "4148")
      (footprint "eagle-import:MINI_MELF")
      (fields
        (field (name "LCSC-PART") "C402260")
        (field (name "MANUFACTURER") "LGE")
        (field (name "MFGPART#") "LL4148")
        (field (name "SPICEPREFIX") "D")
      )
      (libsource (lib "eagle-import") (part "DIODE-MINI-MELF-4148"))
    )
    (comp (ref "G1")
      (value "16M")
      (footprint "eagle-import:SMD3225-4P")
      (fields
        (field (name "LCSC-PART") "C12668")
        (field (name "MANUFACTURER") "Yangxing Tech")
        (field (name "MFGPART#") "X322516MOB4SI")
      )
      (libsource (lib "eagle-import") (part "CRYSTAL-PKGSMD3225-4P-16M"))
    )
    (comp (ref "J1")
      (value "USB-TYPE-C\"")
      (footprint "eagle-import:USB-C-SMD_TYPE-C16PIN")
      (fields
        (field (name "LCSC-PART") "C393939")
        (field (name "MANUFACTURER") "SHOU HAN")
        (field (name "MFGPART#") "TYPE-C16PIN")
      )
      (libsource (lib "eagle-import") (part "USB-TYPE-C{dblquote}"))
    )
    (comp (ref "R1")
      (value "5.1K")
      (footprint "eagle-import:R0402")
      (fields
        (field (name "LCSC-PART") "C325521")
        (field (name "MANUFACTURER") "TyoHM")
        (field (name "MFGPART#") "RMC04025.1K1%N")
      )
      (libsource (lib "eagle-import") (part "R-EU-0402-5.1K"))
    )
    (comp (ref "R2")
      (value "5.1K")
      (footprint "eagle-import:R0402")
      (fields
        (field (name "LCSC-PART") "C325521")
        (field (name "MANUFACTURER") "TyoHM")
        (field (name "MFGPART#") "RMC04025.1K1%N")
      )
      (libsource (lib "eagle-import") (part "R-EU-0402-5.1K"))
    )
    (comp (ref "R3")
      (value "22")
      (footprint "eagle-import:R0402")
      (fields
        (field (name "LCSC-PART") "C163821")
        (field (name "MANUFACTURER") "Walsin Tech Corp")
        (field (name "MFGPART#") "WR04X22R0FTL")
      )
      (libsource (lib "eagle-import") (part "R-EU-0402-22"))
    )
    (comp (ref "R4")
      (value "22")
      (footprint "eagle-import:R0402")
      (fields
        (field (name "LCSC-PART") "C163821")
        (field (name "MANUFACTURER") "Walsin Tech Corp")
        (field (name "MFGPART#") "WR04X22R0FTL")
      )
      (libsource (lib "eagle-import") (part "R-EU-0402-22"))
    )
    (comp (ref "R5")
      (value "10K")
      (footprint "eagle-import:R0402")
      (fields
        (field (name "LCSC-PART") "C140214")
        (field (name "MANUFACTURER") "FH(Guangdong Fenghua Advanced Tech)")
        (field (name "MFGPART#") "RC-02W103JT ")
      )
      (libsource (lib "eagle-import") (part "R-EU-0402-10K"))
    )
    (comp (ref "R6")
      (value "300")
      (footprint "eagle-import:R0402")
      (fields
        (field (name "LCSC-PART") "C911734")
        (field (name "MANUFACTURER") "TA-I Tech")
        (field (name "MFGPART#") "RMS04FT3000")
      )
      (libsource (lib "eagle-import") (part "R-EU-0402-300"))
    )
    (comp (ref "S1")
      (value "MX_SWITCH")
      (footprint "eagle-import:MX_SWITCH")
      (fields (field (name "SPICEPREFIX") "B"))
      (libsource (lib "eagle-import") (part "MX_SWITCH"))
    )
    (comp (ref "S2")
      (value "MX_SWITCH")
      (footprint "eagle-import:MX_SWITCH")
      (fields (field (name "SPICEPREFIX") "B"))
      (libsource (lib "eagle-import") (part "MX_SWITCH"))
    )
    (comp (ref "S3")
      (value "MX_SWITCH")
      (footprint "eagle-import:MX_SWITCH")
      (fields (field (name "SPICEPREFIX") "B"))
      (libsource (lib "eagle-import") (part "MX_SWITCH"))
    )
    (comp (ref "S4")
      (value "MX_SWITCH")
      (footprint "eagle-import:MX_SWITCH")
      (fields (field (name "SPICEPREFIX") "B"))
      (libsource (lib "eagle-import") (part "MX_SWITCH"))
    )
    (comp (ref "S5")
      (value "MX_SWITCH")
      (footprint "eagle-import:MX_SWITCH")
      (fields (field (name "SPICEPREFIX") "B"))
      (libsource (lib "eagle-import") (part "MX_SWITCH"))
    )
    (comp (ref "S6")
      (value "MX_SWITCH")
      (footprint "eagle-import:MX_SWITCH")
      (fields (field (name "SPICEPREFIX") "B"))
      (libsource (lib "eagle-import") (part "MX_SWITCH"))
    )
    (comp (ref "S7")
      (value "MX_SWITCH")
      (footprint "eagle-import:MX_SWITCH")
      (fields (field (name "SPICEPREFIX") "B"))
      (libsource (lib "eagle-import") (part "MX_SWITCH"))
    )
    (comp (ref "S8")
      (value "MX_SWITCH")
      (footprint "eagle-import:MX_SWITCH")
      (fields (field (name "SPICEPREFIX") "B"))
      (libsource (lib "eagle-import") (part "MX_SWITCH"))
    )
    (comp (ref "S9")
      (value "MX_SWITCH")
      (footprint "eagle-import:MX_SWITCH")
      (fields (field (name "SPICEPREFIX") "B"))
      (libsource (lib "eagle-import") (part "MX_SWITCH"))
    )
    (comp (ref "S10")
      (value "MX_SWITCH")
      (footprint "eagle-import:MX_SWITCH")
      (fields (field (name "SPICEPREFIX") "B"))
      (libsource (lib "eagle-import") (part "MX_SWITCH"))
    )
    (comp (ref "S11")
      (value "MX_SWITCH")
      (footprint "eagle-import:MX_SWITCH")
      (fields (field (name "SPICEPREFIX") "B"))
      (libsource (lib "eagle-import") (part "MX_SWITCH"))
    )
    (comp (ref "S12")
      (value "MX_SWITCH")
      (footprint "eagle-import:MX_SWITCH")
      (fields (field (name "SPICEPREFIX") "B"))
      (libsource (lib "eagle-import") (part "MX_SWITCH"))
    )
    (comp (ref "S13")
      (value "MX_SWITCH")
      (footprint "eagle-import:MX_SWITCH")
      (fields (field (name "SPICEPREFIX") "B"))
      (libsource (lib "eagle-import") (part "MX_SWITCH"))
    )
    (comp (ref "S14")
      (value "MX_SWITCH")
      (footprint "eagle-import:MX_SWITCH")
      (fields (field (name "SPICEPREFIX") "B"))
      (libsource (lib "eagle-import") (part "MX_SWITCH"))
    )
    (comp (ref "S15")
      (value "MX_SWITCH")
      (footprint "eagle-import:MX_SWITCH")
      (fields (field (name "SPICEPREFIX") "B"))
      (libsource (lib "eagle-import") (part "MX_SWITCH"))
    )
    (comp (ref "S16")
      (value "MX_SWITCH")
      (footprint "eagle-import:MX_SWITCH")
      (fields (field (name "SPICEPREFIX") "B"))
      (libsource (lib "eagle-import") (part "MX_SWITCH"))
    )
    (comp (ref "S17")
      (value "MX_SWITCH")
      (footprint "eagle-import:MX_SWITCH")
      (fields (field (name "SPICEPREFIX") "B"))
      (libsource (lib "eagle-import") (part "MX_SWITCH"))
    )
    (comp (ref "S18")
      (value "MX_SWITCH")
      (footprint "eagle-import:MX_SWITCH")
      (fields (field (name "SPICEPREFIX") "B"))
      (libsource (lib "eagle-import") (part "MX_SWITCH"))
    )
    (comp (ref "S19")
      (value "MX_SWITCH")
      (footprint "eagle-import:MX_SWITCH")
      (fields (field (name "SPICEPREFIX") "B"))
      (libsource (lib "eagle-import") (part "MX_SWITCH"))
    )
    (comp (ref "S20")
      (value "MX_SWITCH")
      (footprint "eagle-import:MX_SWITCH")
      (fields (field (name "SPICEPREFIX") "B"))
      (libsource (lib "eagle-import") (part "MX_SWITCH"))
    )
    (comp (ref "S21")
      (value "MX_SWITCH")
      (footprint "eagle-import:MX_SWITCH")
      (fields (field (name "SPICEPREFIX") "B"))
      (libsource (lib "eagle-import") (part "MX_SWITCH"))
    )
    (comp (ref "S22")
      (value "MX_SWITCH")
      (footprint "eagle-import:MX_SWITCH")
      (fields (field (name "SPICEPREFIX") "B"))
      (libsource (lib "eagle-import") (part "MX_SWITCH"))
    )
    (comp (ref "S23")
      (value "MX_SWITCH")
      (footprint "eagle-import:MX_SWITCH")
      (fields (field (name "SPICEPREFIX") "B"))
      (libsource (lib "eagle-import") (part "MX_SWITCH"))
    )
    (comp (ref "S24")
      (value "MX_SWITCH")
      (footprint "eagle-import:MX_SWITCH")
      (fields (field (name "SPICEPREFIX") "B"))
      (libsource (lib "eagle-import") (part "MX_SWITCH"))
    )
    (comp (ref "S25")
      (value "MX_SWITCH")
      (footprint "eagle-import:MX_SWITCH")
      (fields (field (name "SPICEPREFIX") "B"))
      (libsource (lib "eagle-import") (part "MX_SWITCH"))
    )
    (comp (ref "S26")
      (value "MX_SWITCH")
      (footprint "eagle-import:MX_SWITCH")
      (fields (field (name "SPICEPREFIX") "B"))
      (libsource (lib "eagle-import") (part "MX_SWITCH"))
    )
    (comp (ref "S27")
      (value "MX_SWITCH")
      (footprint "eagle-import:MX_SWITCH")
      (fields (field (name "SPICEPREFIX") "B"))
      (libsource (lib "eagle-import") (part "MX_SWITCH"))
    )
    (comp (ref "S28")
      (value "MX_SWITCH")
      (footprint "eagle-import:MX_SWITCH")
      (fields (field (name "SPICEPREFIX") "B"))
      (libsource (lib "eagle-import") (part "MX_SWITCH"))
    )
    (comp (ref "S29")
      (value "MX_SWITCH")
      (footprint "eagle-import:MX_SWITCH")
      (fields (field (name "SPICEPREFIX") "B"))
      (libsource (lib "eagle-import") (part "MX_SWITCH"))
    )
    (comp (ref "S30")
      (value "MX_SWITCH")
      (footprint "eagle-import:MX_SWITCH")
      (fields (field (name "SPICEPREFIX") "B"))
      (libsource (lib "eagle-import") (part "MX_SWITCH"))
    )
    (comp (ref "S31")
      (value "MX_SWITCH")
      (footprint "eagle-import:MX_SWITCH")
      (fields (field (name "SPICEPREFIX") "B"))
      (libsource (lib "eagle-import") (part "MX_SWITCH"))
    )
    (comp (ref "S32")
      (value "MX_SWITCH")
      (footprint "eagle-import:MX_SWITCH")
      (fields (field (name "SPICEPREFIX") "B"))
      (libsource (lib "eagle-import") (part "MX_SWITCH"))
    )
    (comp (ref "S33")
      (value "MX_SWITCH")
      (footprint "eagle-import:MX_SWITCH")
      (fields (field (name "SPICEPREFIX") "B"))
      (libsource (lib "eagle-import") (part "MX_SWITCH"))
    )
    (comp (ref "S34")
      (value "MX_SWITCH")
      (footprint "eagle-import:MX_SWITCH")
      (fields (field (name "SPICEPREFIX") "B"))
      (libsource (lib "eagle-import") (part "MX_SWITCH"))
    )
    (comp (ref "S35")
      (value "MX_SWITCH")
      (footprint "eagle-import:MX_SWITCH")
      (fields (field (name "SPICEPREFIX") "B"))
      (libsource (lib "eagle-import") (part "MX_SWITCH"))
    )
    (comp (ref "S36")
      (value "MX_SWITCH")
      (footprint "eagle-import:MX_SWITCH")
      (fields (field (name "SPICEPREFIX") "B"))
      (libsource (lib "eagle-import") (part "MX_SWITCH"))
    )
    (comp (ref "S37")
      (value "MX_SWITCH")
      (footprint "eagle-import:MX_SWITCH")
      (fields (field (name "SPICEPREFIX") "B"))
      (libsource (lib "eagle-import") (part "MX_SWITCH"))
    )
    (comp (ref "S38")
      (value "MX_SWITCH")
      (footprint "eagle-import:MX_SWITCH")
      (fields (field (name "SPICEPREFIX") "B"))
      (libsource (lib "eagle-import") (part "MX_SWITCH"))
    )
    (comp (ref "S39")
      (value "MX_SWITCH")
      (footprint "eagle-import:MX_SWITCH")
      (fields (field (name "SPICEPREFIX") "B"))
      (libsource (lib "eagle-import") (part "MX_SWITCH"))
    )
    (comp (ref "S40")
      (value "MX_SWITCH")
      (footprint "eagle-import:MX_SWITCH")
      (fields (field (name "SPICEPREFIX") "B"))
      (libsource (lib "eagle-import") (part "MX_SWITCH"))
    )
    (comp (ref "S41")
      (value "MX_SWITCH")
      (footprint "eagle-import:MX_SWITCH")
      (fields (field (name "SPICEPREFIX") "B"))
      (libsource (lib "eagle-import") (part "MX_SWITCH"))
    )
    (comp (ref "S42")
      (value "MX_SWITCH")
      (footprint "eagle-import:MX_SWITCH")
      (fields (field (name "SPICEPREFIX") "B"))
      (libsource (lib "eagle-import") (part "MX_SWITCH"))
    )
    (comp (ref "S43")
      (value "MX_SWITCH")
      (footprint "eagle-import:MX_SWITCH")
      (fields (field (name "SPICEPREFIX") "B"))
      (libsource (lib "eagle-import") (part "MX_SWITCH"))
    )
    (comp (ref "S44")
      (value "MX_SWITCH")
      (footprint "eagle-import:MX_SWITCH")
      (fields (field (name "SPICEPREFIX") "B"))
      (libsource (lib "eagle-import") (part "MX_SWITCH"))
    )
    (comp (ref "S45")
      (value "MX_SWITCH")
      (footprint "eagle-import:MX_SWITCH")
      (fields (field (name "SPICEPREFIX") "B"))
      (libsource (lib "eagle-import") (part "MX_SWITCH"))
    )
    (comp (ref "S46")
      (value "MX_SWITCH")
      (footprint "eagle-import:MX_SWITCH")
      (fields (field (name "SPICEPREFIX") "B"))
      (libsource (lib "eagle-import") (part "MX_SWITCH"))
    )
    (comp (ref "S47")
      (value "MX_SWITCH")
      (footprint "eagle-import:MX_SWITCH")
      (fields (field (name "SPICEPREFIX") "B"))
      (libsource (lib "eagle-import") (part "MX_SWITCH"))
    )
    (comp (ref "S48")
      (value "SWITCH-SMD,3*4")
      (footprint "eagle-import:SMD,3X4X2.0MM")
      (fields
        (field (name "LCSC-PART") "C455280")
        (field (name "MANUFACTURER") "XUNPU")
        (field (name "MFGPART#") "TS-1088R-02026")
      )
      (libsource (lib "eagle-import") (part "SWITCH-SMD,34"))
    )
    (comp (ref "U$1")
      (value "JST-8PIN-SR")
      (footprint "eagle-import:JST-SR-8PIN")
      (fields
        (field (name "LCSC-PART") "C160407")
        (field (name "MANUFACTURER") "JST Sales America")
        (field (name "MFGPART#") "SM08B-SRSS-TB(LF)(SN)")
      )
      (libsource (lib "eagle-import") (part "JST-8PIN-SR"))
    )
    (comp (ref "U1")
      (value "ATMEGA32U4-MUR")
      (footprint "eagle-import:QFN-44_7X7X05P")
      (fields (field (name "LCSC-PART") "C45874") (field (name "MANUFACTURER") "Microchip Tech"))
      (libsource (lib "eagle-import") (part "ATMEGA32U4-MUR"))
    )
    (comp (ref "U2")
      (value "M2.5-HOLE")
      (footprint "eagle-import:M2.5")
      (libsource (lib "eagle-import") (part "M2.5-HOLE"))
    )
    (comp (ref "U3")
      (value "M2.5-HOLE")
      (footprint "eagle-import:M2.5")
      (libsource (lib "eagle-import") (part "M2.5-HOLE"))
    )
    (comp (ref "U4")
      (value "M2.5-HOLE")
      (footprint "eagle-import:M2.5")
      (libsource (lib "eagle-import") (part "M2.5-HOLE"))
    )
    (comp (ref "U5")
      (value "M2.5-HOLE")
      (footprint "eagle-import:M2.5")
      (libsource (lib "eagle-import") (part "M2.5-HOLE"))
    )
    (comp (ref "U6")
      (value "M2.5-HOLE")
      (footprint "eagle-import:M2.5")
      (libsource (lib "eagle-import") (part "M2.5-HOLE"))
    )
    (comp (ref "U7")
      (value "M2.5-HOLE")
      (footprint "eagle-import:M2.5")
      (libsource (lib "eagle-import") (part "M2.5-HOLE"))
    )
    (comp (ref "U8")
      (value "M2.5-HOLE")
      (footprint "eagle-import:M2.5")
      (libsource (lib "eagle-import") (part "M2.5-HOLE"))
    )
  )
  (nets
    (net (code "1") (name "+5V") (class "Default")
      (node (ref "C1") (pin "P$2") (pinfunction "P$2_P$2") (pintype "bidirectional"))
      (node (ref "C10") (pin "P$2") (pinfunction "P$2_P$2") (pintype "bidirectional"))
      (node (ref "C11") (pin "P$2") (pinfunction "P$2_P$2") (pintype "bidirectional"))
      (node (ref "C12") (pin "P$2") (pinfunction "P$2_P$2") (pintype "bidirectional"))
      (node (ref "C13") (pin "P$1") (pinfunction "P$1_P$1") (pintype "bidirectional"))
      (node (ref "C14") (pin "P$1") (pinfunction "P$1_P$1") (pintype "bidirectional"))
      (node (ref "C15") (pin "P$1") (pinfunction "P$1_P$1") (pintype "bidirectional"))
      (node (ref "C16") (pin "P$1") (pinfunction "P$1_P$1") (pintype "bidirectional"))
      (node (ref "C17") (pin "P$1") (pinfunction "P$1_P$1") (pintype "bidirectional"))
      (node (ref "C18") (pin "P$1") (pinfunction "P$1_P$1") (pintype "bidirectional"))
      (node (ref "C19") (pin "P$1") (pinfunction "P$1_P$1") (pintype "bidirectional"))
      (node (ref "C2") (pin "P$2") (pinfunction "P$2_P$2") (pintype "bidirectional"))
      (node (ref "C20") (pin "P$1") (pinfunction "P$1_P$1") (pintype "bidirectional"))
      (node (ref "C21") (pin "P$1") (pinfunction "P$1_P$1") (pintype "bidirectional"))
      (node (ref "C22") (pin "P$1") (pinfunction "P$1_P$1") (pintype "bidirectional"))
      (node (ref "C23") (pin "P$1") (pinfunction "P$1_P$1") (pintype "bidirectional"))
      (node (ref "C24") (pin "P$1") (pinfunction "P$1_P$1") (pintype "bidirectional"))
      (node (ref "C25") (pin "P$2") (pinfunction "P$2_P$2") (pintype "bidirectional"))
      (node (ref "C26") (pin "P$2") (pinfunction "P$2_P$2") (pintype "bidirectional"))
      (node (ref "C27") (pin "P$2") (pinfunction "P$2_P$2") (pintype "bidirectional"))
      (node (ref "C28") (pin "P$2") (pinfunction "P$2_P$2") (pintype "bidirectional"))
      (node (ref "C29") (pin "P$2") (pinfunction "P$2_P$2") (pintype "bidirectional"))
      (node (ref "C3") (pin "P$2") (pinfunction "P$2_P$2") (pintype "bidirectional"))
      (node (ref "C30") (pin "P$2") (pinfunction "P$2_P$2") (pintype "bidirectional"))
      (node (ref "C31") (pin "P$2") (pinfunction "P$2_P$2") (pintype "bidirectional"))
      (node (ref "C32") (pin "P$2") (pinfunction "P$2_P$2") (pintype "bidirectional"))
      (node (ref "C33") (pin "P$2") (pinfunction "P$2_P$2") (pintype "bidirectional"))
      (node (ref "C34") (pin "P$2") (pinfunction "P$2_P$2") (pintype "bidirectional"))
      (node (ref "C35") (pin "P$2") (pinfunction "P$2_P$2") (pintype "bidirectional"))
      (node (ref "C36") (pin "P$2") (pinfunction "P$2_P$2") (pintype "bidirectional"))
      (node (ref "C37") (pin "P$1") (pinfunction "P$1_P$1") (pintype "bidirectional"))
      (node (ref "C38") (pin "P$1") (pinfunction "P$1_P$1") (pintype "bidirectional"))
      (node (ref "C39") (pin "P$1") (pinfunction "P$1_P$1") (pintype "bidirectional"))
      (node (ref "C4") (pin "P$2") (pinfunction "P$2_P$2") (pintype "bidirectional"))
      (node (ref "C40") (pin "P$1") (pinfunction "P$1_P$1") (pintype "bidirectional"))
      (node (ref "C41") (pin "P$1") (pinfunction "P$1_P$1") (pintype "bidirectional"))
      (node (ref "C42") (pin "P$1") (pinfunction "P$1_P$1") (pintype "bidirectional"))
      (node (ref "C43") (pin "P$1") (pinfunction "P$1_P$1") (pintype "bidirectional"))
      (node (ref "C44") (pin "P$1") (pinfunction "P$1_P$1") (pintype "bidirectional"))
      (node (ref "C45") (pin "P$1") (pinfunction "P$1_P$1") (pintype "bidirectional"))
      (node (ref "C46") (pin "P$1") (pinfunction "P$1_P$1") (pintype "bidirectional"))
      (node (ref "C47") (pin "P$1") (pinfunction "P$1_P$1") (pintype "bidirectional"))
      (node (ref "C5") (pin "P$2") (pinfunction "P$2_P$2") (pintype "bidirectional"))
      (node (ref "C51") (pin "P$1") (pinfunction "P$1_P$1") (pintype "bidirectional"))
      (node (ref "C52") (pin "P$1") (pinfunction "P$1_P$1") (pintype "bidirectional"))
      (node (ref "C53") (pin "P$1") (pinfunction "P$1_P$1") (pintype "bidirectional"))
      (node (ref "C54") (pin "P$1") (pinfunction "P$1_P$1") (pintype "bidirectional"))
      (node (ref "C6") (pin "P$2") (pinfunction "P$2_P$2") (pintype "bidirectional"))
      (node (ref "C7") (pin "P$2") (pinfunction "P$2_P$2") (pintype "bidirectional"))
      (node (ref "C8") (pin "P$2") (pinfunction "P$2_P$2") (pintype "bidirectional"))
      (node (ref "C9") (pin "P$2") (pinfunction "P$2_P$2") (pintype "bidirectional"))
      (node (ref "CR1") (pin "P$1") (pinfunction "VIN_P$1") (pintype "bidirectional"))
      (node (ref "CR10") (pin "P$1") (pinfunction "VIN_P$1") (pintype "bidirectional"))
      (node (ref "CR11") (pin "P$1") (pinfunction "VIN_P$1") (pintype "bidirectional"))
      (node (ref "CR12") (pin "P$1") (pinfunction "VIN_P$1") (pintype "bidirectional"))
      (node (ref "CR13") (pin "P$1") (pinfunction "VIN_P$1") (pintype "bidirectional"))
      (node (ref "CR14") (pin "P$1") (pinfunction "VIN_P$1") (pintype "bidirectional"))
      (node (ref "CR15") (pin "P$1") (pinfunction "VIN_P$1") (pintype "bidirectional"))
      (node (ref "CR16") (pin "P$1") (pinfunction "VIN_P$1") (pintype "bidirectional"))
      (node (ref "CR17") (pin "P$1") (pinfunction "VIN_P$1") (pintype "bidirectional"))
      (node (ref "CR18") (pin "P$1") (pinfunction "VIN_P$1") (pintype "bidirectional"))
      (node (ref "CR19") (pin "P$1") (pinfunction "VIN_P$1") (pintype "bidirectional"))
      (node (ref "CR2") (pin "P$1") (pinfunction "VIN_P$1") (pintype "bidirectional"))
      (node (ref "CR20") (pin "P$1") (pinfunction "VIN_P$1") (pintype "bidirectional"))
      (node (ref "CR21") (pin "P$1") (pinfunction "VIN_P$1") (pintype "bidirectional"))
      (node (ref "CR22") (pin "P$1") (pinfunction "VIN_P$1") (pintype "bidirectional"))
      (node (ref "CR23") (pin "P$1") (pinfunction "VIN_P$1") (pintype "bidirectional"))
      (node (ref "CR24") (pin "P$1") (pinfunction "VIN_P$1") (pintype "bidirectional"))
      (node (ref "CR25") (pin "P$1") (pinfunction "VIN_P$1") (pintype "bidirectional"))
      (node (ref "CR26") (pin "P$1") (pinfunction "VIN_P$1") (pintype "bidirectional"))
      (node (ref "CR27") (pin "P$1") (pinfunction "VIN_P$1") (pintype "bidirectional"))
      (node (ref "CR28") (pin "P$1") (pinfunction "VIN_P$1") (pintype "bidirectional"))
      (node (ref "CR29") (pin "P$1") (pinfunction "VIN_P$1") (pintype "bidirectional"))
      (node (ref "CR3") (pin "P$1") (pinfunction "VIN_P$1") (pintype "bidirectional"))
      (node (ref "CR30") (pin "P$1") (pinfunction "VIN_P$1") (pintype "bidirectional"))
      (node (ref "CR31") (pin "P$1") (pinfunction "VIN_P$1") (pintype "bidirectional"))
      (node (ref "CR32") (pin "P$1") (pinfunction "VIN_P$1") (pintype "bidirectional"))
      (node (ref "CR33") (pin "P$1") (pinfunction "VIN_P$1") (pintype "bidirectional"))
      (node (ref "CR34") (pin "P$1") (pinfunction "VIN_P$1") (pintype "bidirectional"))
      (node (ref "CR35") (pin "P$1") (pinfunction "VIN_P$1") (pintype "bidirectional"))
      (node (ref "CR36") (pin "P$1") (pinfunction "VIN_P$1") (pintype "bidirectional"))
      (node (ref "CR37") (pin "P$1") (pinfunction "VIN_P$1") (pintype "bidirectional"))
      (node (ref "CR38") (pin "P$1") (pinfunction "VIN_P$1") (pintype "bidirectional"))
      (node (ref "CR39") (pin "P$1") (pinfunction "VIN_P$1") (pintype "bidirectional"))
      (node (ref "CR4") (pin "P$1") (pinfunction "VIN_P$1") (pintype "bidirectional"))
      (node (ref "CR40") (pin "P$1") (pinfunction "VIN_P$1") (pintype "bidirectional"))
      (node (ref "CR41") (pin "P$1") (pinfunction "VIN_P$1") (pintype "bidirectional"))
      (node (ref "CR42") (pin "P$1") (pinfunction "VIN_P$1") (pintype "bidirectional"))
      (node (ref "CR43") (pin "P$1") (pinfunction "VIN_P$1") (pintype "bidirectional"))
      (node (ref "CR44") (pin "P$1") (pinfunction "VIN_P$1") (pintype "bidirectional"))
      (node (ref "CR45") (pin "P$1") (pinfunction "VIN_P$1") (pintype "bidirectional"))
      (node (ref "CR46") (pin "P$1") (pinfunction "VIN_P$1") (pintype "bidirectional"))
      (node (ref "CR47") (pin "P$1") (pinfunction "VIN_P$1") (pintype "bidirectional"))
      (node (ref "CR5") (pin "P$1") (pinfunction "VIN_P$1") (pintype "bidirectional"))
      (node (ref "CR6") (pin "P$1") (pinfunction "VIN_P$1") (pintype "bidirectional"))
      (node (ref "CR7") (pin "P$1") (pinfunction "VIN_P$1") (pintype "bidirectional"))
      (node (ref "CR8") (pin "P$1") (pinfunction "VIN_P$1") (pintype "bidirectional"))
      (node (ref "CR9") (pin "P$1") (pinfunction "VIN_P$1") (pintype "bidirectional"))
      (node (ref "J1") (pin "A4B9") (pinfunction "VBUS_A4B9") (pintype "bidirectional"))
      (node (ref "J1") (pin "B4A9") (pinfunction "VBUS_B4A9") (pintype "bidirectional"))
      (node (ref "R5") (pin "P$1") (pinfunction "1_P$1") (pintype "passive"))
      (node (ref "U$1") (pin "P$1") (pinfunction "J0_P$1") (pintype "bidirectional"))
      (node (ref "U1") (pin "P$14") (pinfunction "VCC_P$14") (pintype "bidirectional"))
      (node (ref "U1") (pin "P$2") (pinfunction "UVCC_P$2") (pintype "bidirectional"))
      (node (ref "U1") (pin "P$24") (pinfunction "AVCC_P$24") (pintype "bidirectional"))
      (node (ref "U1") (pin "P$34") (pinfunction "VCC_P$34") (pintype "bidirectional"))
      (node (ref "U1") (pin "P$44") (pinfunction "AVCC_P$44") (pintype "bidirectional"))
      (node (ref "U1") (pin "P$7") (pinfunction "VBUS_P$7") (pintype "bidirectional"))
    )
    (net (code "2") (name "BL-CS") (class "Default")
      (node (ref "U$1") (pin "P$5") (pinfunction "J4_P$5") (pintype "bidirectional"))
      (node (ref "U1") (pin "P$28") (pinfunction "PB4_P$28") (pintype "bidirectional"))
    )
    (net (code "3") (name "BL-IRQ") (class "Default")
      (node (ref "U$1") (pin "P$4") (pinfunction "J3_P$4") (pintype "bidirectional"))
      (node (ref "U1") (pin "P$1") (pinfunction "PE6_P$1") (pintype "bidirectional"))
    )
    (net (code "4") (name "BL-RST") (class "Default")
      (node (ref "U$1") (pin "P$3") (pinfunction "J2_P$3") (pintype "bidirectional"))
      (node (ref "U1") (pin "P$25") (pinfunction "PD4_P$25") (pintype "bidirectional"))
    )
    (net (code "5") (name "COL_1") (class "Default")
      (node (ref "S1") (pin "P$2") (pinfunction "P$2_P$2") (pintype "bidirectional"))
      (node (ref "S13") (pin "P$2") (pinfunction "P$2_P$2") (pintype "bidirectional"))
      (node (ref "S25") (pin "P$2") (pinfunction "P$2_P$2") (pintype "bidirectional"))
      (node (ref "S37") (pin "P$2") (pinfunction "P$2_P$2") (pintype "bidirectional"))
      (node (ref "U1") (pin "P$40") (pinfunction "PF1_P$40") (pintype "bidirectional"))
    )
    (net (code "6") (name "COL_2") (class "Default")
      (node (ref "S14") (pin "P$2") (pinfunction "P$2_P$2") (pintype "bidirectional"))
      (node (ref "S2") (pin "P$2") (pinfunction "P$2_P$2") (pintype "bidirectional"))
      (node (ref "S26") (pin "P$2") (pinfunction "P$2_P$2") (pintype "bidirectional"))
      (node (ref "S38") (pin "P$2") (pinfunction "P$2_P$2") (pintype "bidirectional"))
      (node (ref "U1") (pin "P$33") (pinfunction "PE2_P$33") (pintype "bidirectional"))
    )
    (net (code "7") (name "COL_3") (class "Default")
      (node (ref "S15") (pin "P$2") (pinfunction "P$2_P$2") (pintype "bidirectional"))
      (node (ref "S27") (pin "P$2") (pinfunction "P$2_P$2") (pintype "bidirectional"))
      (node (ref "S3") (pin "P$2") (pinfunction "P$2_P$2") (pintype "bidirectional"))
      (node (ref "S39") (pin "P$2") (pinfunction "P$2_P$2") (pintype "bidirectional"))
      (node (ref "U1") (pin "P$12") (pinfunction "PB7_P$12") (pintype "bidirectional"))
    )
    (net (code "8") (name "COL_4") (class "Default")
      (node (ref "S16") (pin "P$2") (pinfunction "P$2_P$2") (pintype "bidirectional"))
      (node (ref "S28") (pin "P$2") (pinfunction "P$2_P$2") (pintype "bidirectional"))
      (node (ref "S4") (pin "P$2") (pinfunction "P$2_P$2") (pintype "bidirectional"))
      (node (ref "S40") (pin "P$2") (pinfunction "P$2_P$2") (pintype "bidirectional"))
      (node (ref "U1") (pin "P$8") (pinfunction "PB0_P$8") (pintype "bidirectional"))
    )
    (net (code "9") (name "COL_5") (class "Default")
      (node (ref "S17") (pin "P$2") (pinfunction "P$2_P$2") (pintype "bidirectional"))
      (node (ref "S29") (pin "P$2") (pinfunction "P$2_P$2") (pintype "bidirectional"))
      (node (ref "S41") (pin "P$2") (pinfunction "P$2_P$2") (pintype "bidirectional"))
      (node (ref "S5") (pin "P$2") (pinfunction "P$2_P$2") (pintype "bidirectional"))
      (node (ref "U1") (pin "P$18") (pinfunction "PD0_P$18") (pintype "bidirectional"))
    )
    (net (code "10") (name "COL_6") (class "Default")
      (node (ref "S18") (pin "P$2") (pinfunction "P$2_P$2") (pintype "bidirectional"))
      (node (ref "S30") (pin "P$2") (pinfunction "P$2_P$2") (pintype "bidirectional"))
      (node (ref "S6") (pin "P$2") (pinfunction "P$2_P$2") (pintype "bidirectional"))
      (node (ref "U1") (pin "P$19") (pinfunction "PD1_P$19") (pintype "bidirectional"))
    )
    (net (code "11") (name "COL_7") (class "Default")
      (node (ref "S19") (pin "P$2") (pinfunction "P$2_P$2") (pintype "bidirectional"))
      (node (ref "S31") (pin "P$2") (pinfunction "P$2_P$2") (pintype "bidirectional"))
      (node (ref "S42") (pin "P$2") (pinfunction "P$2_P$2") (pintype "bidirectional"))
      (node (ref "S7") (pin "P$2") (pinfunction "P$2_P$2") (pintype "bidirectional"))
      (node (ref "U1") (pin "P$26") (pinfunction "PD6_P$26") (pintype "bidirectional"))
    )
    (net (code "12") (name "COL_8") (class "Default")
      (node (ref "S20") (pin "P$2") (pinfunction "P$2_P$2") (pintype "bidirectional"))
      (node (ref "S32") (pin "P$2") (pinfunction "P$2_P$2") (pintype "bidirectional"))
      (node (ref "S43") (pin "P$2") (pinfunction "P$2_P$2") (pintype "bidirectional"))
      (node (ref "S8") (pin "P$2") (pinfunction "P$2_P$2") (pintype "bidirectional"))
      (node (ref "U1") (pin "P$27") (pinfunction "PD7_P$27") (pintype "bidirectional"))
    )
    (net (code "13") (name "COL_9") (class "Default")
      (node (ref "S21") (pin "P$2") (pinfunction "P$2_P$2") (pintype "bidirectional"))
      (node (ref "S33") (pin "P$2") (pinfunction "P$2_P$2") (pintype "bidirectional"))
      (node (ref "S44") (pin "P$2") (pinfunction "P$2_P$2") (pintype "bidirectional"))
      (node (ref "S9") (pin "P$2") (pinfunction "P$2_P$2") (pintype "bidirectional"))
      (node (ref "U1") (pin "P$29") (pinfunction "PB5_P$29") (pintype "bidirectional"))
    )
    (net (code "14") (name "COL_10") (class "Default")
      (node (ref "S10") (pin "P$2") (pinfunction "P$2_P$2") (pintype "bidirectional"))
      (node (ref "S22") (pin "P$2") (pinfunction "P$2_P$2") (pintype "bidirectional"))
      (node (ref "S34") (pin "P$2") (pinfunction "P$2_P$2") (pintype "bidirectional"))
      (node (ref "S45") (pin "P$2") (pinfunction "P$2_P$2") (pintype "bidirectional"))
      (node (ref "U1") (pin "P$30") (pinfunction "PB6_P$30") (pintype "bidirectional"))
    )
    (net (code "15") (name "COL_11") (class "Default")
      (node (ref "S11") (pin "P$2") (pinfunction "P$2_P$2") (pintype "bidirectional"))
      (node (ref "S23") (pin "P$2") (pinfunction "P$2_P$2") (pintype "bidirectional"))
      (node (ref "S35") (pin "P$2") (pinfunction "P$2_P$2") (pintype "bidirectional"))
      (node (ref "S46") (pin "P$2") (pinfunction "P$2_P$2") (pintype "bidirectional"))
      (node (ref "U1") (pin "P$31") (pinfunction "PC6_P$31") (pintype "bidirectional"))
    )
    (net (code "16") (name "COL_12") (class "Default")
      (node (ref "S12") (pin "P$2") (pinfunction "P$2_P$2") (pintype "bidirectional"))
      (node (ref "S24") (pin "P$2") (pinfunction "P$2_P$2") (pintype "bidirectional"))
      (node (ref "S36") (pin "P$2") (pinfunction "P$2_P$2") (pintype "bidirectional"))
      (node (ref "S47") (pin "P$2") (pinfunction "P$2_P$2") (pintype "bidirectional"))
      (node (ref "U1") (pin "P$32") (pinfunction "PC7_P$32") (pintype "bidirectional"))
    )
    (net (code "17") (name "D+") (class "Default")
      (node (ref "J1") (pin "A6") (pinfunction "DP1_A6") (pintype "bidirectional"))
      (node (ref "J1") (pin "B6") (pinfunction "DP2_B6") (pintype "bidirectional"))
      (node (ref "R3") (pin "P$1") (pinfunction "1_P$1") (pintype "passive"))
    )
    (net (code "18") (name "D-") (class "Default")
      (node (ref "J1") (pin "A7") (pinfunction "DN1_A7") (pintype "bidirectional"))
      (node (ref "J1") (pin "B7") (pinfunction "DN2_B7") (pintype "bidirectional"))
      (node (ref "R4") (pin "P$1") (pinfunction "1_P$1") (pintype "passive"))
    )
    (net (code "19") (name "GND") (class "Default")
      (node (ref "C1") (pin "P$1") (pinfunction "P$1_P$1") (pintype "bidirectional"))
      (node (ref "C10") (pin "P$1") (pinfunction "P$1_P$1") (pintype "bidirectional"))
      (node (ref "C11") (pin "P$1") (pinfunction "P$1_P$1") (pintype "bidirectional"))
      (node (ref "C12") (pin "P$1") (pinfunction "P$1_P$1") (pintype "bidirectional"))
      (node (ref "C13") (pin "P$2") (pinfunction "P$2_P$2") (pintype "bidirectional"))
      (node (ref "C14") (pin "P$2") (pinfunction "P$2_P$2") (pintype "bidirectional"))
      (node (ref "C15") (pin "P$2") (pinfunction "P$2_P$2") (pintype "bidirectional"))
      (node (ref "C16") (pin "P$2") (pinfunction "P$2_P$2") (pintype "bidirectional"))
      (node (ref "C17") (pin "P$2") (pinfunction "P$2_P$2") (pintype "bidirectional"))
      (node (ref "C18") (pin "P$2") (pinfunction "P$2_P$2") (pintype "bidirectional"))
      (node (ref "C19") (pin "P$2") (pinfunction "P$2_P$2") (pintype "bidirectional"))
      (node (ref "C2") (pin "P$1") (pinfunction "P$1_P$1") (pintype "bidirectional"))
      (node (ref "C20") (pin "P$2") (pinfunction "P$2_P$2") (pintype "bidirectional"))
      (node (ref "C21") (pin "P$2") (pinfunction "P$2_P$2") (pintype "bidirectional"))
      (node (ref "C22") (pin "P$2") (pinfunction "P$2_P$2") (pintype "bidirectional"))
      (node (ref "C23") (pin "P$2") (pinfunction "P$2_P$2") (pintype "bidirectional"))
      (node (ref "C24") (pin "P$2") (pinfunction "P$2_P$2") (pintype "bidirectional"))
      (node (ref "C25") (pin "P$1") (pinfunction "P$1_P$1") (pintype "bidirectional"))
      (node (ref "C26") (pin "P$1") (pinfunction "P$1_P$1") (pintype "bidirectional"))
      (node (ref "C27") (pin "P$1") (pinfunction "P$1_P$1") (pintype "bidirectional"))
      (node (ref "C28") (pin "P$1") (pinfunction "P$1_P$1") (pintype "bidirectional"))
      (node (ref "C29") (pin "P$1") (pinfunction "P$1_P$1") (pintype "bidirectional"))
      (node (ref "C3") (pin "P$1") (pinfunction "P$1_P$1") (pintype "bidirectional"))
      (node (ref "C30") (pin "P$1") (pinfunction "P$1_P$1") (pintype "bidirectional"))
      (node (ref "C31") (pin "P$1") (pinfunction "P$1_P$1") (pintype "bidirectional"))
      (node (ref "C32") (pin "P$1") (pinfunction "P$1_P$1") (pintype "bidirectional"))
      (node (ref "C33") (pin "P$1") (pinfunction "P$1_P$1") (pintype "bidirectional"))
      (node (ref "C34") (pin "P$1") (pinfunction "P$1_P$1") (pintype "bidirectional"))
      (node (ref "C35") (pin "P$1") (pinfunction "P$1_P$1") (pintype "bidirectional"))
      (node (ref "C36") (pin "P$1") (pinfunction "P$1_P$1") (pintype "bidirectional"))
      (node (ref "C37") (pin "P$2") (pinfunction "P$2_P$2") (pintype "bidirectional"))
      (node (ref "C38") (pin "P$2") (pinfunction "P$2_P$2") (pintype "bidirectional"))
      (node (ref "C39") (pin "P$2") (pinfunction "P$2_P$2") (pintype "bidirectional"))
      (node (ref "C4") (pin "P$1") (pinfunction "P$1_P$1") (pintype "bidirectional"))
      (node (ref "C40") (pin "P$2") (pinfunction "P$2_P$2") (pintype "bidirectional"))
      (node (ref "C41") (pin "P$2") (pinfunction "P$2_P$2") (pintype "bidirectional"))
      (node (ref "C42") (pin "P$2") (pinfunction "P$2_P$2") (pintype "bidirectional"))
      (node (ref "C43") (pin "P$2") (pinfunction "P$2_P$2") (pintype "bidirectional"))
      (node (ref "C44") (pin "P$2") (pinfunction "P$2_P$2") (pintype "bidirectional"))
      (node (ref "C45") (pin "P$2") (pinfunction "P$2_P$2") (pintype "bidirectional"))
      (node (ref "C46") (pin "P$2") (pinfunction "P$2_P$2") (pintype "bidirectional"))
      (node (ref "C47") (pin "P$2") (pinfunction "P$2_P$2") (pintype "bidirectional"))
      (node (ref "C48") (pin "P$1") (pinfunction "P$1_P$1") (pintype "bidirectional"))
      (node (ref "C49") (pin "P$1") (pinfunction "P$1_P$1") (pintype "bidirectional"))
      (node (ref "C5") (pin "P$1") (pinfunction "P$1_P$1") (pintype "bidirectional"))
      (node (ref "C50") (pin "P$2") (pinfunction "P$2_P$2") (pintype "bidirectional"))
      (node (ref "C51") (pin "P$2") (pinfunction "P$2_P$2") (pintype "bidirectional"))
      (node (ref "C52") (pin "P$2") (pinfunction "P$2_P$2") (pintype "bidirectional"))
      (node (ref "C53") (pin "P$2") (pinfunction "P$2_P$2") (pintype "bidirectional"))
      (node (ref "C54") (pin "P$2") (pinfunction "P$2_P$2") (pintype "bidirectional"))
      (node (ref "C6") (pin "P$1") (pinfunction "P$1_P$1") (pintype "bidirectional"))
      (node (ref "C7") (pin "P$1") (pinfunction "P$1_P$1") (pintype "bidirectional"))
      (node (ref "C8") (pin "P$1") (pinfunction "P$1_P$1") (pintype "bidirectional"))
      (node (ref "C9") (pin "P$1") (pinfunction "P$1_P$1") (pintype "bidirectional"))
      (node (ref "CR1") (pin "P$4") (pinfunction "GND_P$4") (pintype "bidirectional"))
      (node (ref "CR10") (pin "P$4") (pinfunction "GND_P$4") (pintype "bidirectional"))
      (node (ref "CR11") (pin "P$4") (pinfunction "GND_P$4") (pintype "bidirectional"))
      (node (ref "CR12") (pin "P$4") (pinfunction "GND_P$4") (pintype "bidirectional"))
      (node (ref "CR13") (pin "P$4") (pinfunction "GND_P$4") (pintype "bidirectional"))
      (node (ref "CR14") (pin "P$4") (pinfunction "GND_P$4") (pintype "bidirectional"))
      (node (ref "CR15") (pin "P$4") (pinfunction "GND_P$4") (pintype "bidirectional"))
      (node (ref "CR16") (pin "P$4") (pinfunction "GND_P$4") (pintype "bidirectional"))
      (node (ref "CR17") (pin "P$4") (pinfunction "GND_P$4") (pintype "bidirectional"))
      (node (ref "CR18") (pin "P$4") (pinfunction "GND_P$4") (pintype "bidirectional"))
      (node (ref "CR19") (pin "P$4") (pinfunction "GND_P$4") (pintype "bidirectional"))
      (node (ref "CR2") (pin "P$4") (pinfunction "GND_P$4") (pintype "bidirectional"))
      (node (ref "CR20") (pin "P$4") (pinfunction "GND_P$4") (pintype "bidirectional"))
      (node (ref "CR21") (pin "P$4") (pinfunction "GND_P$4") (pintype "bidirectional"))
      (node (ref "CR22") (pin "P$4") (pinfunction "GND_P$4") (pintype "bidirectional"))
      (node (ref "CR23") (pin "P$4") (pinfunction "GND_P$4") (pintype "bidirectional"))
      (node (ref "CR24") (pin "P$4") (pinfunction "GND_P$4") (pintype "bidirectional"))
      (node (ref "CR25") (pin "P$4") (pinfunction "GND_P$4") (pintype "bidirectional"))
      (node (ref "CR26") (pin "P$4") (pinfunction "GND_P$4") (pintype "bidirectional"))
      (node (ref "CR27") (pin "P$4") (pinfunction "GND_P$4") (pintype "bidirectional"))
      (node (ref "CR28") (pin "P$4") (pinfunction "GND_P$4") (pintype "bidirectional"))
      (node (ref "CR29") (pin "P$4") (pinfunction "GND_P$4") (pintype "bidirectional"))
      (node (ref "CR3") (pin "P$4") (pinfunction "GND_P$4") (pintype "bidirectional"))
      (node (ref "CR30") (pin "P$4") (pinfunction "GND_P$4") (pintype "bidirectional"))
      (node (ref "CR31") (pin "P$4") (pinfunction "GND_P$4") (pintype "bidirectional"))
      (node (ref "CR32") (pin "P$4") (pinfunction "GND_P$4") (pintype "bidirectional"))
      (node (ref "CR33") (pin "P$4") (pinfunction "GND_P$4") (pintype "bidirectional"))
      (node (ref "CR34") (pin "P$4") (pinfunction "GND_P$4") (pintype "bidirectional"))
      (node (ref "CR35") (pin "P$4") (pinfunction "GND_P$4") (pintype "bidirectional"))
      (node (ref "CR36") (pin "P$4") (pinfunction "GND_P$4") (pintype "bidirectional"))
      (node (ref "CR37") (pin "P$4") (pinfunction "GND_P$4") (pintype "bidirectional"))
      (node (ref "CR38") (pin "P$4") (pinfunction "GND_P$4") (pintype "bidirectional"))
      (node (ref "CR39") (pin "P$4") (pinfunction "GND_P$4") (pintype "bidirectional"))
      (node (ref "CR4") (pin "P$4") (pinfunction "GND_P$4") (pintype "bidirectional"))
      (node (ref "CR40") (pin "P$4") (pinfunction "GND_P$4") (pintype "bidirectional"))
      (node (ref "CR41") (pin "P$4") (pinfunction "GND_P$4") (pintype "bidirectional"))
      (node (ref "CR42") (pin "P$4") (pinfunction "GND_P$4") (pintype "bidirectional"))
      (node (ref "CR43") (pin "P$4") (pinfunction "GND_P$4") (pintype "bidirectional"))
      (node (ref "CR44") (pin "P$4") (pinfunction "GND_P$4") (pintype "bidirectional"))
      (node (ref "CR45") (pin "P$4") (pinfunction "GND_P$4") (pintype "bidirectional"))
      (node (ref "CR46") (pin "P$4") (pinfunction "GND_P$4") (pintype "bidirectional"))
      (node (ref "CR47") (pin "P$4") (pinfunction "GND_P$4") (pintype "bidirectional"))
      (node (ref "CR5") (pin "P$4") (pinfunction "GND_P$4") (pintype "bidirectional"))
      (node (ref "CR6") (pin "P$4") (pinfunction "GND_P$4") (pintype "bidirectional"))
      (node (ref "CR7") (pin "P$4") (pinfunction "GND_P$4") (pintype "bidirectional"))
      (node (ref "CR8") (pin "P$4") (pinfunction "GND_P$4") (pintype "bidirectional"))
      (node (ref "CR9") (pin "P$4") (pinfunction "GND_P$4") (pintype "bidirectional"))
      (node (ref "G1") (pin "P$2") (pinfunction "P2_P$2") (pintype "bidirectional"))
      (node (ref "G1") (pin "P$4") (pinfunction "P2_P$4") (pintype "bidirectional"))
      (node (ref "J1") (pin "A1B12") (pinfunction "GND_A1B12") (pintype "bidirectional"))
      (node (ref "J1") (pin "B1A12") (pinfunction "GND_B1A12") (pintype "bidirectional"))
      (node (ref "J1") (pin "SHIELD") (pinfunction "SHIELD_SHIELD") (pintype "bidirectional"))
      (node (ref "J1") (pin "SHIELD1") (pinfunction "SHIELD_SHIELD1") (pintype "bidirectional"))
      (node (ref "J1") (pin "SHIELD2") (pinfunction "SHIELD_SHIELD2") (pintype "bidirectional"))
      (node (ref "J1") (pin "SHIELD3") (pinfunction "SHIELD_SHIELD3") (pintype "bidirectional"))
      (node (ref "R1") (pin "P$1") (pinfunction "1_P$1") (pintype "passive"))
      (node (ref "R2") (pin "P$1") (pinfunction "1_P$1") (pintype "passive"))
      (node (ref "S48") (pin "P$2") (pinfunction "P$2_P$2") (pintype "bidirectional"))
      (node (ref "U$1") (pin "P$2") (pinfunction "J1_P$2") (pintype "bidirectional"))
      (node (ref "U1") (pin "P$15") (pinfunction "GND_P$15") (pintype "bidirectional"))
      (node (ref "U1") (pin "P$23") (pinfunction "GND_P$23") (pintype "bidirectional"))
      (node (ref "U1") (pin "P$35") (pinfunction "GND_P$35") (pintype "bidirectional"))
      (node (ref "U1") (pin "P$43") (pinfunction "GND_P$43") (pintype "bidirectional"))
      (node (ref "U1") (pin "P$45") (pinfunction "GND_P$45") (pintype "bidirectional"))
      (node (ref "U1") (pin "P$5") (pinfunction "UGND_P$5") (pintype "bidirectional"))
      (node (ref "U2") (pin "P$1") (pinfunction "P1_P$1") (pintype "bidirectional"))
      (node (ref "U3") (pin "P$1") (pinfunction "P1_P$1") (pintype "bidirectional"))
      (node (ref "U4") (pin "P$1") (pinfunction "P1_P$1") (pintype "bidirectional"))
      (node (ref "U5") (pin "P$1") (pinfunction "P1_P$1") (pintype "bidirectional"))
      (node (ref "U6") (pin "P$1") (pinfunction "P1_P$1") (pintype "bidirectional"))
      (node (ref "U7") (pin "P$1") (pinfunction "P1_P$1") (pintype "bidirectional"))
      (node (ref "U8") (pin "P$1") (pinfunction "P1_P$1") (pintype "bidirectional"))
    )
    (net (code "20") (name "MISO") (class "Default")
      (node (ref "U$1") (pin "P$7") (pinfunction "J6_P$7") (pintype "bidirectional"))
      (node (ref "U1") (pin "P$11") (pinfunction "PB3_P$11") (pintype "bidirectional"))
    )
    (net (code "21") (name "MOSI") (class "Default")
      (node (ref "U$1") (pin "P$6") (pinfunction "J5_P$6") (pintype "bidirectional"))
      (node (ref "U1") (pin "P$10") (pinfunction "PB2_P$10") (pintype "bidirectional"))
    )
    (net (code "22") (name "Net-(CR1-DIN)") (class "Default")
      (node (ref "CR1") (pin "P$3") (pinfunction "DIN_P$3") (pintype "bidirectional"))
      (node (ref "CR2") (pin "P$2") (pinfunction "DOUT_P$2") (pintype "bidirectional"))
    )
    (net (code "23") (name "Net-(CR2-DIN)") (class "Default")
      (node (ref "CR2") (pin "P$3") (pinfunction "DIN_P$3") (pintype "bidirectional"))
      (node (ref "CR3") (pin "P$2") (pinfunction "DOUT_P$2") (pintype "bidirectional"))
    )
    (net (code "24") (name "Net-(CR3-DIN)") (class "Default")
      (node (ref "CR3") (pin "P$3") (pinfunction "DIN_P$3") (pintype "bidirectional"))
      (node (ref "CR4") (pin "P$2") (pinfunction "DOUT_P$2") (pintype "bidirectional"))
    )
    (net (code "25") (name "Net-(CR4-DIN)") (class "Default")
      (node (ref "CR4") (pin "P$3") (pinfunction "DIN_P$3") (pintype "bidirectional"))
      (node (ref "CR5") (pin "P$2") (pinfunction "DOUT_P$2") (pintype "bidirectional"))
    )
    (net (code "26") (name "Net-(CR5-DIN)") (class "Default")
      (node (ref "CR5") (pin "P$3") (pinfunction "DIN_P$3") (pintype "bidirectional"))
      (node (ref "CR6") (pin "P$2") (pinfunction "DOUT_P$2") (pintype "bidirectional"))
    )
    (net (code "27") (name "Net-(CR6-DIN)") (class "Default")
      (node (ref "CR6") (pin "P$3") (pinfunction "DIN_P$3") (pintype "bidirectional"))
      (node (ref "CR7") (pin "P$2") (pinfunction "DOUT_P$2") (pintype "bidirectional"))
    )
    (net (code "28") (name "Net-(CR7-DIN)") (class "Default")
      (node (ref "CR7") (pin "P$3") (pinfunction "DIN_P$3") (pintype "bidirectional"))
      (node (ref "CR8") (pin "P$2") (pinfunction "DOUT_P$2") (pintype "bidirectional"))
    )
    (net (code "29") (name "Net-(CR8-DIN)") (class "Default")
      (node (ref "CR8") (pin "P$3") (pinfunction "DIN_P$3") (pintype "bidirectional"))
      (node (ref "CR9") (pin "P$2") (pinfunction "DOUT_P$2") (pintype "bidirectional"))
    )
    (net (code "30") (name "Net-(CR10-DIN)") (class "Default")
      (node (ref "CR10") (pin "P$3") (pinfunction "DIN_P$3") (pintype "bidirectional"))
      (node (ref "CR11") (pin "P$2") (pinfunction "DOUT_P$2") (pintype "bidirectional"))
    )
    (net (code "31") (name "Net-(CR10-DOUT)") (class "Default")
      (node (ref "CR10") (pin "P$2") (pinfunction "DOUT_P$2") (pintype "bidirectional"))
      (node (ref "CR9") (pin "P$3") (pinfunction "DIN_P$3") (pintype "bidirectional"))
    )
    (net (code "32") (name "Net-(CR11-DIN)") (class "Default")
      (node (ref "CR11") (pin "P$3") (pinfunction "DIN_P$3") (pintype "bidirectional"))
      (node (ref "CR12") (pin "P$2") (pinfunction "DOUT_P$2") (pintype "bidirectional"))
    )
    (net (code "33") (name "Net-(CR12-DIN)") (class "Default")
      (node (ref "CR12") (pin "P$3") (pinfunction "DIN_P$3") (pintype "bidirectional"))
      (node (ref "CR24") (pin "P$2") (pinfunction "DOUT_P$2") (pintype "bidirectional"))
    )
    (net (code "34") (name "Net-(CR13-DIN)") (class "Default")
      (node (ref "CR13") (pin "P$3") (pinfunction "DIN_P$3") (pintype "bidirectional"))
      (node (ref "CR25") (pin "P$2") (pinfunction "DOUT_P$2") (pintype "bidirectional"))
    )
    (net (code "35") (name "Net-(CR13-DOUT)") (class "Default")
      (node (ref "CR13") (pin "P$2") (pinfunction "DOUT_P$2") (pintype "bidirectional"))
      (node (ref "CR14") (pin "P$3") (pinfunction "DIN_P$3") (pintype "bidirectional"))
    )
    (net (code "36") (name "Net-(CR14-DOUT)") (class "Default")
      (node (ref "CR14") (pin "P$2") (pinfunction "DOUT_P$2") (pintype "bidirectional"))
      (node (ref "CR15") (pin "P$3") (pinfunction "DIN_P$3") (pintype "bidirectional"))
    )
    (net (code "37") (name "Net-(CR15-DOUT)") (class "Default")
      (node (ref "CR15") (pin "P$2") (pinfunction "DOUT_P$2") (pintype "bidirectional"))
      (node (ref "CR16") (pin "P$3") (pinfunction "DIN_P$3") (pintype "bidirectional"))
    )
    (net (code "38") (name "Net-(CR16-DOUT)") (class "Default")
      (node (ref "CR16") (pin "P$2") (pinfunction "DOUT_P$2") (pintype "bidirectional"))
      (node (ref "CR17") (pin "P$3") (pinfunction "DIN_P$3") (pintype "bidirectional"))
    )
    (net (code "39") (name "Net-(CR17-DOUT)") (class "Default")
      (node (ref "CR17") (pin "P$2") (pinfunction "DOUT_P$2") (pintype "bidirectional"))
      (node (ref "CR18") (pin "P$3") (pinfunction "DIN_P$3") (pintype "bidirectional"))
    )
    (net (code "40") (name "Net-(CR18-DOUT)") (class "Default")
      (node (ref "CR18") (pin "P$2") (pinfunction "DOUT_P$2") (pintype "bidirectional"))
      (node (ref "CR19") (pin "P$3") (pinfunction "DIN_P$3") (pintype "bidirectional"))
    )
    (net (code "41") (name "Net-(CR19-DOUT)") (class "Default")
      (node (ref "CR19") (pin "P$2") (pinfunction "DOUT_P$2") (pintype "bidirectional"))
      (node (ref "CR20") (pin "P$3") (pinfunction "DIN_P$3") (pintype "bidirectional"))
    )
    (net (code "42") (name "Net-(CR20-DOUT)") (class "Default")
      (node (ref "CR20") (pin "P$2") (pinfunction "DOUT_P$2") (pintype "bidirectional"))
      (node (ref "CR21") (pin "P$3") (pinfunction "DIN_P$3") (pintype "bidirectional"))
    )
    (net (code "43") (name "Net-(CR21-DOUT)") (class "Default")
      (node (ref "CR21") (pin "P$2") (pinfunction "DOUT_P$2") (pintype "bidirectional"))
      (node (ref "CR22") (pin "P$3") (pinfunction "DIN_P$3") (pintype "bidirectional"))
    )
    (net (code "44") (name "Net-(CR22-DOUT)") (class "Default")
      (node (ref "CR22") (pin "P$2") (pinfunction "DOUT_P$2") (pintype "bidirectional"))
      (node (ref "CR23") (pin "P$3") (pinfunction "DIN_P$3") (pintype "bidirectional"))
    )
    (net (code "45") (name "Net-(CR23-DOUT)") (class "Default")
      (node (ref "CR23") (pin "P$2") (pinfunction "DOUT_P$2") (pintype "bidirectional"))
      (node (ref "CR24") (pin "P$3") (pinfunction "DIN_P$3") (pintype "bidirectional"))
    )
    (net (code "46") (name "Net-(CR25-DIN)") (class "Default")
      (node (ref "CR25") (pin "P$3") (pinfunction "DIN_P$3") (pintype "bidirectional"))
      (node (ref "CR26") (pin "P$2") (pinfunction "DOUT_P$2") (pintype "bidirectional"))
    )
    (net (code "47") (name "Net-(CR26-DIN)") (class "Default")
      (node (ref "CR26") (pin "P$3") (pinfunction "DIN_P$3") (pintype "bidirectional"))
      (node (ref "CR27") (pin "P$2") (pinfunction "DOUT_P$2") (pintype "bidirectional"))
    )
    (net (code "48") (name "Net-(CR27-DIN)") (class "Default")
      (node (ref "CR27") (pin "P$3") (pinfunction "DIN_P$3") (pintype "bidirectional"))
      (node (ref "CR28") (pin "P$2") (pinfunction "DOUT_P$2") (pintype "bidirectional"))
    )
    (net (code "49") (name "Net-(CR28-DIN)") (class "Default")
      (node (ref "CR28") (pin "P$3") (pinfunction "DIN_P$3") (pintype "bidirectional"))
      (node (ref "CR29") (pin "P$2") (pinfunction "DOUT_P$2") (pintype "bidirectional"))
    )
    (net (code "50") (name "Net-(CR29-DIN)") (class "Default")
      (node (ref "CR29") (pin "P$3") (pinfunction "DIN_P$3") (pintype "bidirectional"))
      (node (ref "CR30") (pin "P$2") (pinfunction "DOUT_P$2") (pintype "bidirectional"))
    )
    (net (code "51") (name "Net-(CR30-DIN)") (class "Default")
      (node (ref "CR30") (pin "P$3") (pinfunction "DIN_P$3") (pintype "bidirectional"))
      (node (ref "CR31") (pin "P$2") (pinfunction "DOUT_P$2") (pintype "bidirectional"))
    )
    (net (code "52") (name "Net-(CR31-DIN)") (class "Default")
      (node (ref "CR31") (pin "P$3") (pinfunction "DIN_P$3") (pintype "bidirectional"))
      (node (ref "CR32") (pin "P$2") (pinfunction "DOUT_P$2") (pintype "bidirectional"))
    )
    (net (code "53") (name "Net-(CR32-DIN)") (class "Default")
      (node (ref "CR32") (pin "P$3") (pinfunction "DIN_P$3") (pintype "bidirectional"))
      (node (ref "CR33") (pin "P$2") (pinfunction "DOUT_P$2") (pintype "bidirectional"))
    )
    (net (code "54") (name "Net-(CR33-DIN)") (class "Default")
      (node (ref "CR33") (pin "P$3") (pinfunction "DIN_P$3") (pintype "bidirectional"))
      (node (ref "CR34") (pin "P$2") (pinfunction "DOUT_P$2") (pintype "bidirectional"))
    )
    (net (code "55") (name "Net-(CR34-DIN)") (class "Default")
      (node (ref "CR34") (pin "P$3") (pinfunction "DIN_P$3") (pintype "bidirectional"))
      (node (ref "CR35") (pin "P$2") (pinfunction "DOUT_P$2") (pintype "bidirectional"))
    )
    (net (code "56") (name "Net-(CR35-DIN)") (class "Default")
      (node (ref "CR35") (pin "P$3") (pinfunction "DIN_P$3") (pintype "bidirectional"))
      (node (ref "CR36") (pin "P$2") (pinfunction "DOUT_P$2") (pintype "bidirectional"))
    )
    (net (code "57") (name "Net-(CR36-DIN)") (class "Default")
      (node (ref "CR36") (pin "P$3") (pinfunction "DIN_P$3") (pintype "bidirectional"))
      (node (ref "CR47") (pin "P$2") (pinfunction "DOUT_P$2") (pintype "bidirectional"))
    )
    (net (code "58") (name "Net-(CR37-DOUT)") (class "Default")
      (node (ref "CR37") (pin "P$2") (pinfunction "DOUT_P$2") (pintype "bidirectional"))
      (node (ref "CR38") (pin "P$3") (pinfunction "DIN_P$3") (pintype "bidirectional"))
    )
    (net (code "59") (name "Net-(CR38-DOUT)") (class "Default")
      (node (ref "CR38") (pin "P$2") (pinfunction "DOUT_P$2") (pintype "bidirectional"))
      (node (ref "CR39") (pin "P$3") (pinfunction "DIN_P$3") (pintype "bidirectional"))
    )
    (net (code "60") (name "Net-(CR39-DOUT)") (class "Default")
      (node (ref "CR39") (pin "P$2") (pinfunction "DOUT_P$2") (pintype "bidirectional"))
      (node (ref "CR40") (pin "P$3") (pinfunction "DIN_P$3") (pintype "bidirectional"))
    )
    (net (code "61") (name "Net-(CR40-DOUT)") (class "Default")
      (node (ref "CR40") (pin "P$2") (pinfunction "DOUT_P$2") (pintype "bidirectional"))
      (node (ref "CR41") (pin "P$3") (pinfunction "DIN_P$3") (pintype "bidirectional"))
    )
    (net (code "62") (name "Net-(CR41-DOUT)") (class "Default")
      (node (ref "CR41") (pin "P$2") (pinfunction "DOUT_P$2") (pintype "bidirectional"))
      (node (ref "CR42") (pin "P$3") (pinfunction "DIN_P$3") (pintype "bidirectional"))
    )
    (net (code "63") (name "Net-(CR42-DOUT)") (class "Default")
      (node (ref "CR42") (pin "P$2") (pinfunction "DOUT_P$2") (pintype "bidirectional"))
      (node (ref "CR43") (pin "P$3") (pinfunction "DIN_P$3") (pintype "bidirectional"))
    )
    (net (code "64") (name "Net-(CR43-DOUT)") (class "Default")
      (node (ref "CR43") (pin "P$2") (pinfunction "DOUT_P$2") (pintype "bidirectional"))
      (node (ref "CR44") (pin "P$3") (pinfunction "DIN_P$3") (pintype "bidirectional"))
    )
    (net (code "65") (name "Net-(CR44-DOUT)") (class "Default")
      (node (ref "CR44") (pin "P$2") (pinfunction "DOUT_P$2") (pintype "bidirectional"))
      (node (ref "CR45") (pin "P$3") (pinfunction "DIN_P$3") (pintype "bidirectional"))
    )
    (net (code "66") (name "Net-(CR45-DOUT)") (class "Default")
      (node (ref "CR45") (pin "P$2") (pinfunction "DOUT_P$2") (pintype "bidirectional"))
      (node (ref "CR46") (pin "P$3") (pinfunction "DIN_P$3") (pintype "bidirectional"))
    )
    (net (code "67") (name "Net-(CR46-DOUT)") (class "Default")
      (node (ref "CR46") (pin "P$2") (pinfunction "DOUT_P$2") (pintype "bidirectional"))
      (node (ref "CR47") (pin "P$3") (pinfunction "DIN_P$3") (pintype "bidirectional"))
    )
    (net (code "68") (name "Net-(D1-+)") (class "Default")
      (node (ref "D1") (pin "P$2") (pinfunction "+_P$2") (pintype "bidirectional"))
      (node (ref "S1") (pin "P$1") (pinfunction "P$1_P$1") (pintype "bidirectional"))
    )
    (net (code "69") (name "Net-(D2-+)") (class "Default")
      (node (ref "D2") (pin "P$2") (pinfunction "+_P$2") (pintype "bidirectional"))
      (node (ref "S2") (pin "P$1") (pinfunction "P$1_P$1") (pintype "bidirectional"))
    )
    (net (code "70") (name "Net-(D3-+)") (class "Default")
      (node (ref "D3") (pin "P$2") (pinfunction "+_P$2") (pintype "bidirectional"))
      (node (ref "S3") (pin "P$1") (pinfunction "P$1_P$1") (pintype "bidirectional"))
    )
    (net (code "71") (name "Net-(D4-+)") (class "Default")
      (node (ref "D4") (pin "P$2") (pinfunction "+_P$2") (pintype "bidirectional"))
      (node (ref "S4") (pin "P$1") (pinfunction "P$1_P$1") (pintype "bidirectional"))
    )
    (net (code "72") (name "Net-(D5-+)") (class "Default")
      (node (ref "D5") (pin "P$2") (pinfunction "+_P$2") (pintype "bidirectional"))
      (node (ref "S5") (pin "P$1") (pinfunction "P$1_P$1") (pintype "bidirectional"))
    )
    (net (code "73") (name "Net-(D6-+)") (class "Default")
      (node (ref "D6") (pin "P$2") (pinfunction "+_P$2") (pintype "bidirectional"))
      (node (ref "S6") (pin "P$1") (pinfunction "P$1_P$1") (pintype "bidirectional"))
    )
    (net (code "74") (name "Net-(D7-+)") (class "Default")
      (node (ref "D7") (pin "P$2") (pinfunction "+_P$2") (pintype "bidirectional"))
      (node (ref "S7") (pin "P$1") (pinfunction "P$1_P$1") (pintype "bidirectional"))
    )
    (net (code "75") (name "Net-(D8-+)") (class "Default")
      (node (ref "D8") (pin "P$2") (pinfunction "+_P$2") (pintype "bidirectional"))
      (node (ref "S8") (pin "P$1") (pinfunction "P$1_P$1") (pintype "bidirectional"))
    )
    (net (code "76") (name "Net-(D9-+)") (class "Default")
      (node (ref "D9") (pin "P$2") (pinfunction "+_P$2") (pintype "bidirectional"))
      (node (ref "S9") (pin "P$1") (pinfunction "P$1_P$1") (pintype "bidirectional"))
    )
    (net (code "77") (name "Net-(D10-+)") (class "Default")
      (node (ref "D10") (pin "P$2") (pinfunction "+_P$2") (pintype "bidirectional"))
      (node (ref "S10") (pin "P$1") (pinfunction "P$1_P$1") (pintype "bidirectional"))
    )
    (net (code "78") (name "Net-(D11-+)") (class "Default")
      (node (ref "D11") (pin "P$2") (pinfunction "+_P$2") (pintype "bidirectional"))
      (node (ref "S11") (pin "P$1") (pinfunction "P$1_P$1") (pintype "bidirectional"))
    )
    (net (code "79") (name "Net-(D12-+)") (class "Default")
      (node (ref "D12") (pin "P$2") (pinfunction "+_P$2") (pintype "bidirectional"))
      (node (ref "S12") (pin "P$1") (pinfunction "P$1_P$1") (pintype "bidirectional"))
    )
    (net (code "80") (name "Net-(D13-+)") (class "Default")
      (node (ref "D13") (pin "P$2") (pinfunction "+_P$2") (pintype "bidirectional"))
      (node (ref "S13") (pin "P$1") (pinfunction "P$1_P$1") (pintype "bidirectional"))
    )
    (net (code "81") (name "Net-(D14-+)") (class "Default")
      (node (ref "D14") (pin "P$2") (pinfunction "+_P$2") (pintype "bidirectional"))
      (node (ref "S14") (pin "P$1") (pinfunction "P$1_P$1") (pintype "bidirectional"))
    )
    (net (code "82") (name "Net-(D15-+)") (class "Default")
      (node (ref "D15") (pin "P$2") (pinfunction "+_P$2") (pintype "bidirectional"))
      (node (ref "S15") (pin "P$1") (pinfunction "P$1_P$1") (pintype "bidirectional"))
    )
    (net (code "83") (name "Net-(D16-+)") (class "Default")
      (node (ref "D16") (pin "P$2") (pinfunction "+_P$2") (pintype "bidirectional"))
      (node (ref "S16") (pin "P$1") (pinfunction "P$1_P$1") (pintype "bidirectional"))
    )
    (net (code "84") (name "Net-(D17-+)") (class "Default")
      (node (ref "D17") (pin "P$2") (pinfunction "+_P$2") (pintype "bidirectional"))
      (node (ref "S17") (pin "P$1") (pinfunction "P$1_P$1") (pintype "bidirectional"))
    )
    (net (code "85") (name "Net-(D18-+)") (class "Default")
      (node (ref "D18") (pin "P$2") (pinfunction "+_P$2") (pintype "bidirectional"))
      (node (ref "S18") (pin "P$1") (pinfunction "P$1_P$1") (pintype "bidirectional"))
    )
    (net (code "86") (name "Net-(D19-+)") (class "Default")
      (node (ref "D19") (pin "P$2") (pinfunction "+_P$2") (pintype "bidirectional"))
      (node (ref "S19") (pin "P$1") (pinfunction "P$1_P$1") (pintype "bidirectional"))
    )
    (net (code "87") (name "Net-(D20-+)") (class "Default")
      (node (ref "D20") (pin "P$2") (pinfunction "+_P$2") (pintype "bidirectional"))
      (node (ref "S20") (pin "P$1") (pinfunction "P$1_P$1") (pintype "bidirectional"))
    )
    (net (code "88") (name "Net-(D21-+)") (class "Default")
      (node (ref "D21") (pin "P$2") (pinfunction "+_P$2") (pintype "bidirectional"))
      (node (ref "S21") (pin "P$1") (pinfunction "P$1_P$1") (pintype "bidirectional"))
    )
    (net (code "89") (name "Net-(D22-+)") (class "Default")
      (node (ref "D22") (pin "P$2") (pinfunction "+_P$2") (pintype "bidirectional"))
      (node (ref "S22") (pin "P$1") (pinfunction "P$1_P$1") (pintype "bidirectional"))
    )
    (net (code "90") (name "Net-(D23-+)") (class "Default")
      (node (ref "D23") (pin "P$2") (pinfunction "+_P$2") (pintype "bidirectional"))
      (node (ref "S23") (pin "P$1") (pinfunction "P$1_P$1") (pintype "bidirectional"))
    )
    (net (code "91") (name "Net-(D24-+)") (class "Default")
      (node (ref "D24") (pin "P$2") (pinfunction "+_P$2") (pintype "bidirectional"))
      (node (ref "S24") (pin "P$1") (pinfunction "P$1_P$1") (pintype "bidirectional"))
    )
    (net (code "92") (name "Net-(D25-+)") (class "Default")
      (node (ref "D25") (pin "P$2") (pinfunction "+_P$2") (pintype "bidirectional"))
      (node (ref "S25") (pin "P$1") (pinfunction "P$1_P$1") (pintype "bidirectional"))
    )
    (net (code "93") (name "Net-(D26-+)") (class "Default")
      (node (ref "D26") (pin "P$2") (pinfunction "+_P$2") (pintype "bidirectional"))
      (node (ref "S26") (pin "P$1") (pinfunction "P$1_P$1") (pintype "bidirectional"))
    )
    (net (code "94") (name "Net-(D27-+)") (class "Default")
      (node (ref "D27") (pin "P$2") (pinfunction "+_P$2") (pintype "bidirectional"))
      (node (ref "S27") (pin "P$1") (pinfunction "P$1_P$1") (pintype "bidirectional"))
    )
    (net (code "95") (name "Net-(D28-+)") (class "Default")
      (node (ref "D28") (pin "P$2") (pinfunction "+_P$2") (pintype "bidirectional"))
      (node (ref "S28") (pin "P$1") (pinfunction "P$1_P$1") (pintype "bidirectional"))
    )
    (net (code "96") (name "Net-(D29-+)") (class "Default")
      (node (ref "D29") (pin "P$2") (pinfunction "+_P$2") (pintype "bidirectional"))
      (node (ref "S29") (pin "P$1") (pinfunction "P$1_P$1") (pintype "bidirectional"))
    )
    (net (code "97") (name "Net-(D30-+)") (class "Default")
      (node (ref "D30") (pin "P$2") (pinfunction "+_P$2") (pintype "bidirectional"))
      (node (ref "S30") (pin "P$1") (pinfunction "P$1_P$1") (pintype "bidirectional"))
    )
    (net (code "98") (name "Net-(D31-+)") (class "Default")
      (node (ref "D31") (pin "P$2") (pinfunction "+_P$2") (pintype "bidirectional"))
      (node (ref "S31") (pin "P$1") (pinfunction "P$1_P$1") (pintype "bidirectional"))
    )
    (net (code "99") (name "Net-(D32-+)") (class "Default")
      (node (ref "D32") (pin "P$2") (pinfunction "+_P$2") (pintype "bidirectional"))
      (node (ref "S32") (pin "P$1") (pinfunction "P$1_P$1") (pintype "bidirectional"))
    )
    (net (code "100") (name "Net-(D33-+)") (class "Default")
      (node (ref "D33") (pin "P$2") (pinfunction "+_P$2") (pintype "bidirectional"))
      (node (ref "S33") (pin "P$1") (pinfunction "P$1_P$1") (pintype "bidirectional"))
    )
    (net (code "101") (name "Net-(D34-+)") (class "Default")
      (node (ref "D34") (pin "P$2") (pinfunction "+_P$2") (pintype "bidirectional"))
      (node (ref "S34") (pin "P$1") (pinfunction "P$1_P$1") (pintype "bidirectional"))
    )
    (net (code "102") (name "Net-(D35-+)") (class "Default")
      (node (ref "D35") (pin "P$2") (pinfunction "+_P$2") (pintype "bidirectional"))
      (node (ref "S35") (pin "P$1") (pinfunction "P$1_P$1") (pintype "bidirectional"))
    )
    (net (code "103") (name "Net-(D36-+)") (class "Default")
      (node (ref "D36") (pin "P$2") (pinfunction "+_P$2") (pintype "bidirectional"))
      (node (ref "S36") (pin "P$1") (pinfunction "P$1_P$1") (pintype "bidirectional"))
    )
    (net (code "104") (name "Net-(D37-+)") (class "Default")
      (node (ref "D37") (pin "P$2") (pinfunction "+_P$2") (pintype "bidirectional"))
      (node (ref "S37") (pin "P$1") (pinfunction "P$1_P$1") (pintype "bidirectional"))
    )
    (net (code "105") (name "Net-(D38-+)") (class "Default")
      (node (ref "D38") (pin "P$2") (pinfunction "+_P$2") (pintype "bidirectional"))
      (node (ref "S38") (pin "P$1") (pinfunction "P$1_P$1") (pintype "bidirectional"))
    )
    (net (code "106") (name "Net-(D39-+)") (class "Default")
      (node (ref "D39") (pin "P$2") (pinfunction "+_P$2") (pintype "bidirectional"))
      (node (ref "S39") (pin "P$1") (pinfunction "P$1_P$1") (pintype "bidirectional"))
    )
    (net (code "107") (name "Net-(D40-+)") (class "Default")
      (node (ref "D40") (pin "P$2") (pinfunction "+_P$2") (pintype "bidirectional"))
      (node (ref "S40") (pin "P$1") (pinfunction "P$1_P$1") (pintype "bidirectional"))
    )
    (net (code "108") (name "Net-(D41-+)") (class "Default")
      (node (ref "D41") (pin "P$2") (pinfunction "+_P$2") (pintype "bidirectional"))
      (node (ref "S41") (pin "P$1") (pinfunction "P$1_P$1") (pintype "bidirectional"))
    )
    (net (code "109") (name "Net-(D42-+)") (class "Default")
      (node (ref "D42") (pin "P$2") (pinfunction "+_P$2") (pintype "bidirectional"))
      (node (ref "S42") (pin "P$1") (pinfunction "P$1_P$1") (pintype "bidirectional"))
    )
    (net (code "110") (name "Net-(D43-+)") (class "Default")
      (node (ref "D43") (pin "P$2") (pinfunction "+_P$2") (pintype "bidirectional"))
      (node (ref "S43") (pin "P$1") (pinfunction "P$1_P$1") (pintype "bidirectional"))
    )
    (net (code "111") (name "Net-(D44-+)") (class "Default")
      (node (ref "D44") (pin "P$2") (pinfunction "+_P$2") (pintype "bidirectional"))
      (node (ref "S44") (pin "P$1") (pinfunction "P$1_P$1") (pintype "bidirectional"))
    )
    (net (code "112") (name "Net-(D45-+)") (class "Default")
      (node (ref "D45") (pin "P$2") (pinfunction "+_P$2") (pintype "bidirectional"))
      (node (ref "S45") (pin "P$1") (pinfunction "P$1_P$1") (pintype "bidirectional"))
    )
    (net (code "113") (name "Net-(D46-+)") (class "Default")
      (node (ref "D46") (pin "P$2") (pinfunction "+_P$2") (pintype "bidirectional"))
      (node (ref "S46") (pin "P$1") (pinfunction "P$1_P$1") (pintype "bidirectional"))
    )
    (net (code "114") (name "Net-(D47-+)") (class "Default")
      (node (ref "D47") (pin "P$2") (pinfunction "+_P$2") (pintype "bidirectional"))
      (node (ref "S47") (pin "P$1") (pinfunction "P$1_P$1") (pintype "bidirectional"))
    )
    (net (code "115") (name "Net-(G1-P0)") (class "Default")
      (node (ref "C49") (pin "P$2") (pinfunction "P$2_P$2") (pintype "bidirectional"))
      (node (ref "G1") (pin "P$1") (pinfunction "P0_P$1") (pintype "bidirectional"))
      (node (ref "U1") (pin "P$17") (pinfunction "XTAL1_P$17") (pintype "bidirectional"))
    )
    (net (code "116") (name "Net-(G1-P1)") (class "Default")
      (node (ref "C50") (pin "P$1") (pinfunction "P$1_P$1") (pintype "bidirectional"))
      (node (ref "G1") (pin "P$3") (pinfunction "P1_P$3") (pintype "bidirectional"))
      (node (ref "U1") (pin "P$16") (pinfunction "XTAL2_P$16") (pintype "bidirectional"))
    )
    (net (code "117") (name "Net-(J1-CC1)") (class "Default")
      (node (ref "J1") (pin "A5") (pinfunction "CC1_A5") (pintype "bidirectional"))
      (node (ref "R2") (pin "P$2") (pinfunction "2_P$2") (pintype "passive"))
    )
    (net (code "118") (name "Net-(J1-CC2)") (class "Default")
      (node (ref "J1") (pin "B5") (pinfunction "CC2_B5") (pintype "bidirectional"))
      (node (ref "R1") (pin "P$2") (pinfunction "2_P$2") (pintype "passive"))
    )
    (net (code "119") (name "Net-(R3-2)") (class "Default")
      (node (ref "R3") (pin "P$2") (pinfunction "2_P$2") (pintype "passive"))
      (node (ref "U1") (pin "P$4") (pinfunction "D+_P$4") (pintype "bidirectional"))
    )
    (net (code "120") (name "Net-(R4-2)") (class "Default")
      (node (ref "R4") (pin "P$2") (pinfunction "2_P$2") (pintype "passive"))
      (node (ref "U1") (pin "P$3") (pinfunction "D-_P$3") (pintype "bidirectional"))
    )
    (net (code "121") (name "Net-(R5-2)") (class "Default")
      (node (ref "R5") (pin "P$2") (pinfunction "2_P$2") (pintype "passive"))
      (node (ref "S48") (pin "P$1") (pinfunction "P$1_P$1") (pintype "bidirectional"))
      (node (ref "U1") (pin "P$13") (pinfunction "RESET_P$13") (pintype "bidirectional"))
    )
    (net (code "122") (name "Net-(R6-1)") (class "Default")
      (node (ref "R6") (pin "P$1") (pinfunction "1_P$1") (pintype "passive"))
      (node (ref "U1") (pin "P$37") (pinfunction "PF6_P$37") (pintype "bidirectional"))
    )
    (net (code "123") (name "Net-(U1-UCAP)") (class "Default")
      (node (ref "C48") (pin "P$2") (pinfunction "P$2_P$2") (pintype "bidirectional"))
      (node (ref "U1") (pin "P$6") (pinfunction "UCAP_P$6") (pintype "bidirectional"))
    )
    (net (code "124") (name "RGB") (class "Default")
      (node (ref "CR37") (pin "P$3") (pinfunction "DIN_P$3") (pintype "bidirectional"))
      (node (ref "R6") (pin "P$2") (pinfunction "2_P$2") (pintype "passive"))
    )
    (net (code "125") (name "ROW_A") (class "Default")
      (node (ref "D1") (pin "P$1") (pinfunction "-_P$1") (pintype "bidirectional"))
      (node (ref "D10") (pin "P$1") (pinfunction "-_P$1") (pintype "bidirectional"))
      (node (ref "D11") (pin "P$1") (pinfunction "-_P$1") (pintype "bidirectional"))
      (node (ref "D12") (pin "P$1") (pinfunction "-_P$1") (pintype "bidirectional"))
      (node (ref "D2") (pin "P$1") (pinfunction "-_P$1") (pintype "bidirectional"))
      (node (ref "D3") (pin "P$1") (pinfunction "-_P$1") (pintype "bidirectional"))
      (node (ref "D4") (pin "P$1") (pinfunction "-_P$1") (pintype "bidirectional"))
      (node (ref "D5") (pin "P$1") (pinfunction "-_P$1") (pintype "bidirectional"))
      (node (ref "D6") (pin "P$1") (pinfunction "-_P$1") (pintype "bidirectional"))
      (node (ref "D7") (pin "P$1") (pinfunction "-_P$1") (pintype "bidirectional"))
      (node (ref "D8") (pin "P$1") (pinfunction "-_P$1") (pintype "bidirectional"))
      (node (ref "D9") (pin "P$1") (pinfunction "-_P$1") (pintype "bidirectional"))
      (node (ref "U1") (pin "P$39") (pinfunction "PF4_P$39") (pintype "bidirectional"))
    )
    (net (code "126") (name "ROW_B") (class "Default")
      (node (ref "D13") (pin "P$1") (pinfunction "-_P$1") (pintype "bidirectional"))
      (node (ref "D14") (pin "P$1") (pinfunction "-_P$1") (pintype "bidirectional"))
      (node (ref "D15") (pin "P$1") (pinfunction "-_P$1") (pintype "bidirectional"))
      (node (ref "D16") (pin "P$1") (pinfunction "-_P$1") (pintype "bidirectional"))
      (node (ref "D17") (pin "P$1") (pinfunction "-_P$1") (pintype "bidirectional"))
      (node (ref "D18") (pin "P$1") (pinfunction "-_P$1") (pintype "bidirectional"))
      (node (ref "D19") (pin "P$1") (pinfunction "-_P$1") (pintype "bidirectional"))
      (node (ref "D20") (pin "P$1") (pinfunction "-_P$1") (pintype "bidirectional"))
      (node (ref "D21") (pin "P$1") (pinfunction "-_P$1") (pintype "bidirectional"))
      (node (ref "D22") (pin "P$1") (pinfunction "-_P$1") (pintype "bidirectional"))
      (node (ref "D23") (pin "P$1") (pinfunction "-_P$1") (pintype "bidirectional"))
      (node (ref "D24") (pin "P$1") (pinfunction "-_P$1") (pintype "bidirectional"))
      (node (ref "U1") (pin "P$41") (pinfunction "PF0_P$41") (pintype "bidirectional"))
    )
    (net (code "127") (name "ROW_C") (class "Default")
      (node (ref "D25") (pin "P$1") (pinfunction "-_P$1") (pintype "bidirectional"))
      (node (ref "D26") (pin "P$1") (pinfunction "-_P$1") (pintype "bidirectional"))
      (node (ref "D27") (pin "P$1") (pinfunction "-_P$1") (pintype "bidirectional"))
      (node (ref "D28") (pin "P$1") (pinfunction "-_P$1") (pintype "bidirectional"))
      (node (ref "D29") (pin "P$1") (pinfunction "-_P$1") (pintype "bidirectional"))
      (node (ref "D30") (pin "P$1") (pinfunction "-_P$1") (pintype "bidirectional"))
      (node (ref "D31") (pin "P$1") (pinfunction "-_P$1") (pintype "bidirectional"))
      (node (ref "D32") (pin "P$1") (pinfunction "-_P$1") (pintype "bidirectional"))
      (node (ref "D33") (pin "P$1") (pinfunction "-_P$1") (pintype "bidirectional"))
      (node (ref "D34") (pin "P$1") (pinfunction "-_P$1") (pintype "bidirectional"))
      (node (ref "D35") (pin "P$1") (pinfunction "-_P$1") (pintype "bidirectional"))
      (node (ref "D36") (pin "P$1") (pinfunction "-_P$1") (pintype "bidirectional"))
      (node (ref "U1") (pin "P$36") (pinfunction "PF7_P$36") (pintype "bidirectional"))
    )
    (net (code "128") (name "ROW_D") (class "Default")
      (node (ref "D37") (pin "P$1") (pinfunction "-_P$1") (pintype "bidirectional"))
      (node (ref "D38") (pin "P$1") (pinfunction "-_P$1") (pintype "bidirectional"))
      (node (ref "D39") (pin "P$1") (pinfunction "-_P$1") (pintype "bidirectional"))
      (node (ref "D40") (pin "P$1") (pinfunction "-_P$1") (pintype "bidirectional"))
      (node (ref "D41") (pin "P$1") (pinfunction "-_P$1") (pintype "bidirectional"))
      (node (ref "D42") (pin "P$1") (pinfunction "-_P$1") (pintype "bidirectional"))
      (node (ref "D43") (pin "P$1") (pinfunction "-_P$1") (pintype "bidirectional"))
      (node (ref "D44") (pin "P$1") (pinfunction "-_P$1") (pintype "bidirectional"))
      (node (ref "D45") (pin "P$1") (pinfunction "-_P$1") (pintype "bidirectional"))
      (node (ref "D46") (pin "P$1") (pinfunction "-_P$1") (pintype "bidirectional"))
      (node (ref "D47") (pin "P$1") (pinfunction "-_P$1") (pintype "bidirectional"))
      (node (ref "U1") (pin "P$38") (pinfunction "PF5_P$38") (pintype "bidirectional"))
    )
    (net (code "129") (name "SCK") (class "Default")
      (node (ref "U$1") (pin "P$8") (pinfunction "J7_P$8") (pintype "bidirectional"))
      (node (ref "U1") (pin "P$9") (pinfunction "PB1_P$9") (pintype "bidirectional"))
    )
    (net (code "130") (name "unconnected-(CR1-DOUT-PadP$2)") (class "Default")
      (node (ref "CR1") (pin "P$2") (pinfunction "DOUT_P$2") (pintype "bidirectional"))
    )
    (net (code "131") (name "unconnected-(J1-SBU1-PadA8)") (class "Default")
      (node (ref "J1") (pin "A8") (pinfunction "SBU1_A8") (pintype "bidirectional"))
    )
    (net (code "132") (name "unconnected-(J1-SBU2-PadB8)") (class "Default")
      (node (ref "J1") (pin "B8") (pinfunction "SBU2_B8") (pintype "bidirectional"))
    )
    (net (code "133") (name "unconnected-(U1-AREF-PadP$42)") (class "Default")
      (node (ref "U1") (pin "P$42") (pinfunction "AREF_P$42") (pintype "bidirectional"))
    )
    (net (code "134") (name "unconnected-(U1-PD2-PadP$20)") (class "Default")
      (node (ref "U1") (pin "P$20") (pinfunction "PD2_P$20") (pintype "bidirectional"))
    )
    (net (code "135") (name "unconnected-(U1-PD3-PadP$21)") (class "Default")
      (node (ref "U1") (pin "P$21") (pinfunction "PD3_P$21") (pintype "bidirectional"))
    )
    (net (code "136") (name "unconnected-(U1-PD5-PadP$22)") (class "Default")
      (node (ref "U1") (pin "P$22") (pinfunction "PD5_P$22") (pintype "bidirectional"))
    )
  )
)
